# OpenDeck-r2_1_0.net
KiCad netlist of a schematic drawn in EAGLE
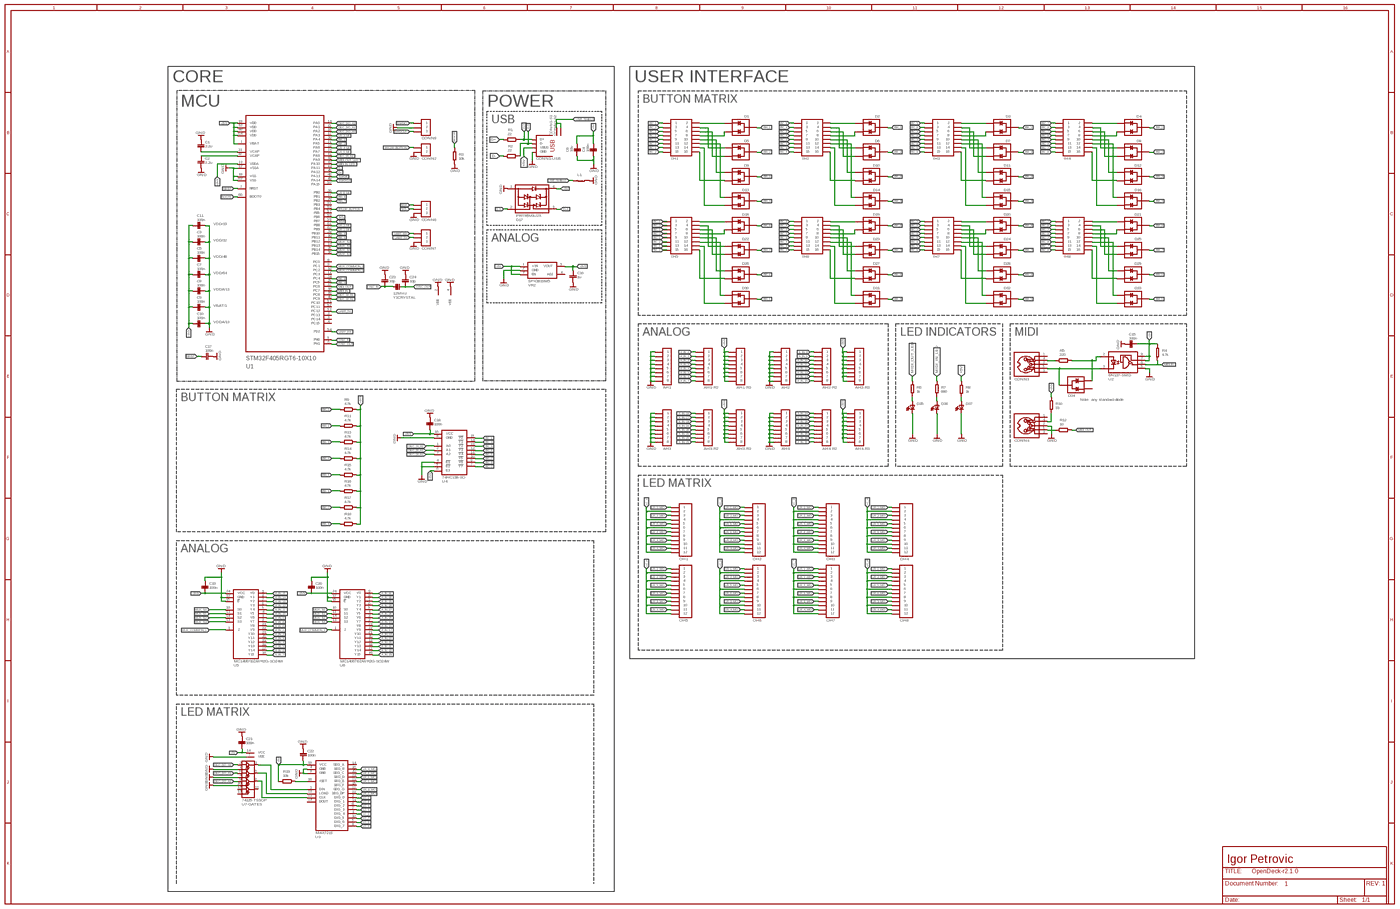
[diagram p0: schematic, sheet 1, overview]
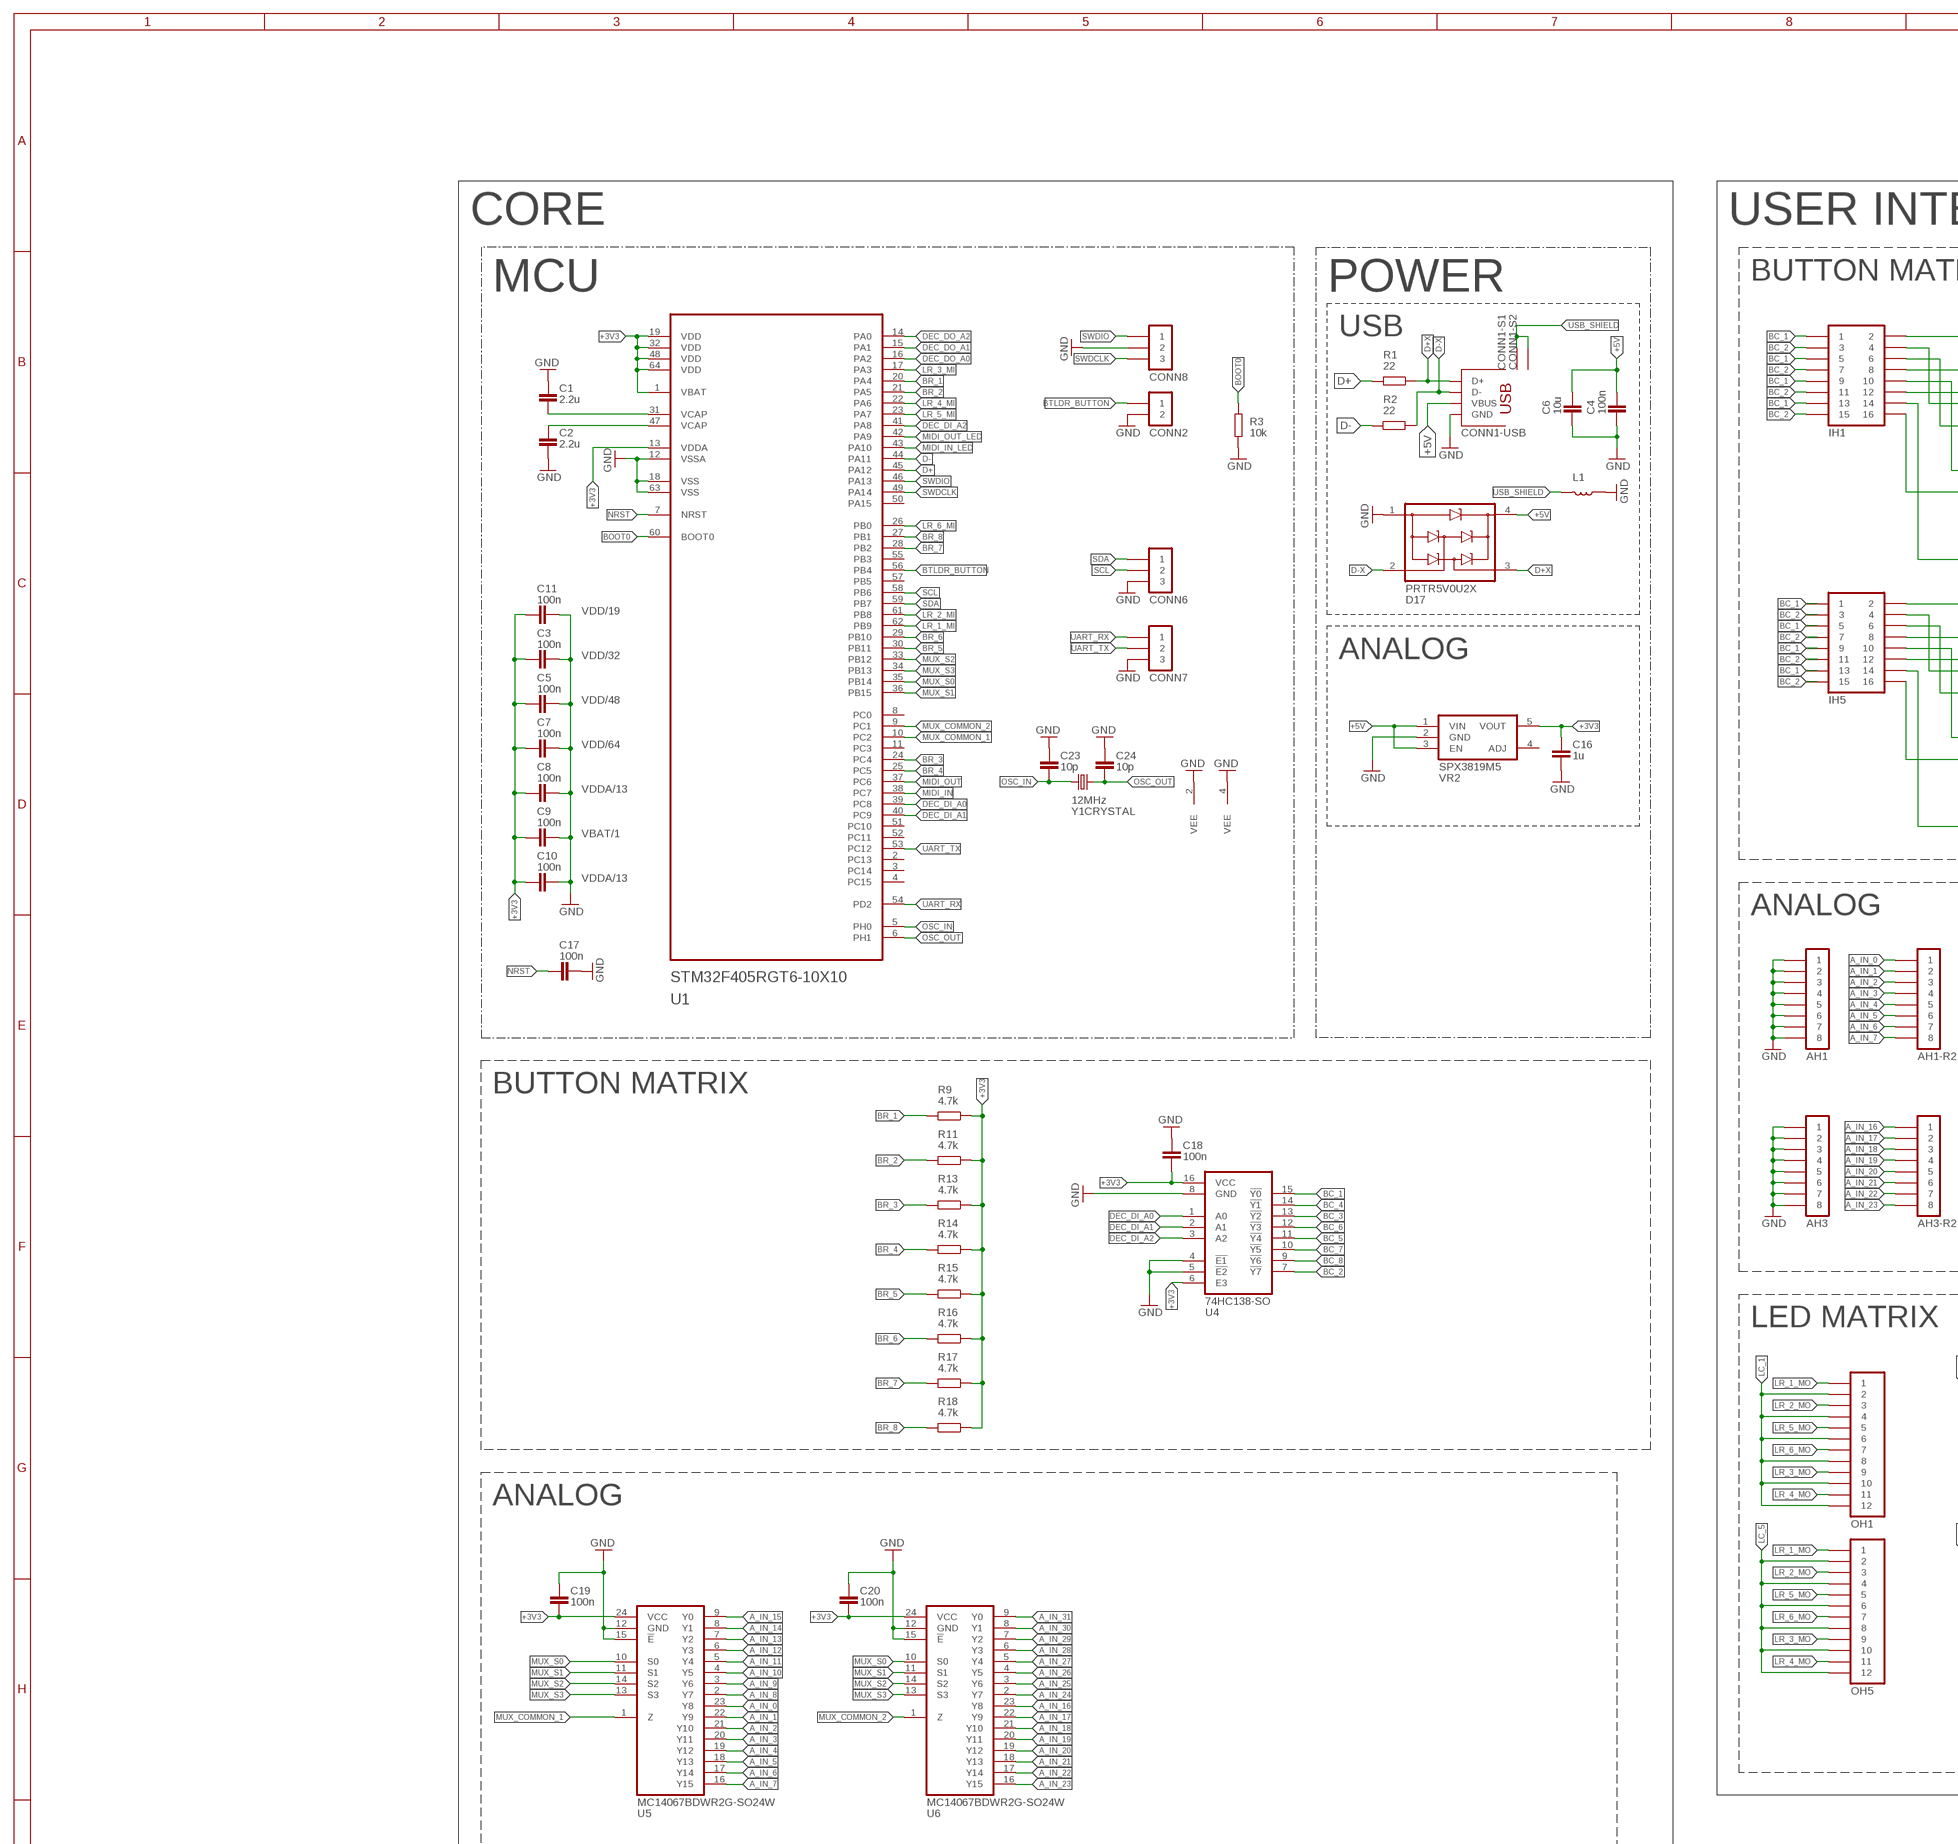
[diagram p1: schematic, sheet 1, part 1 of 4]
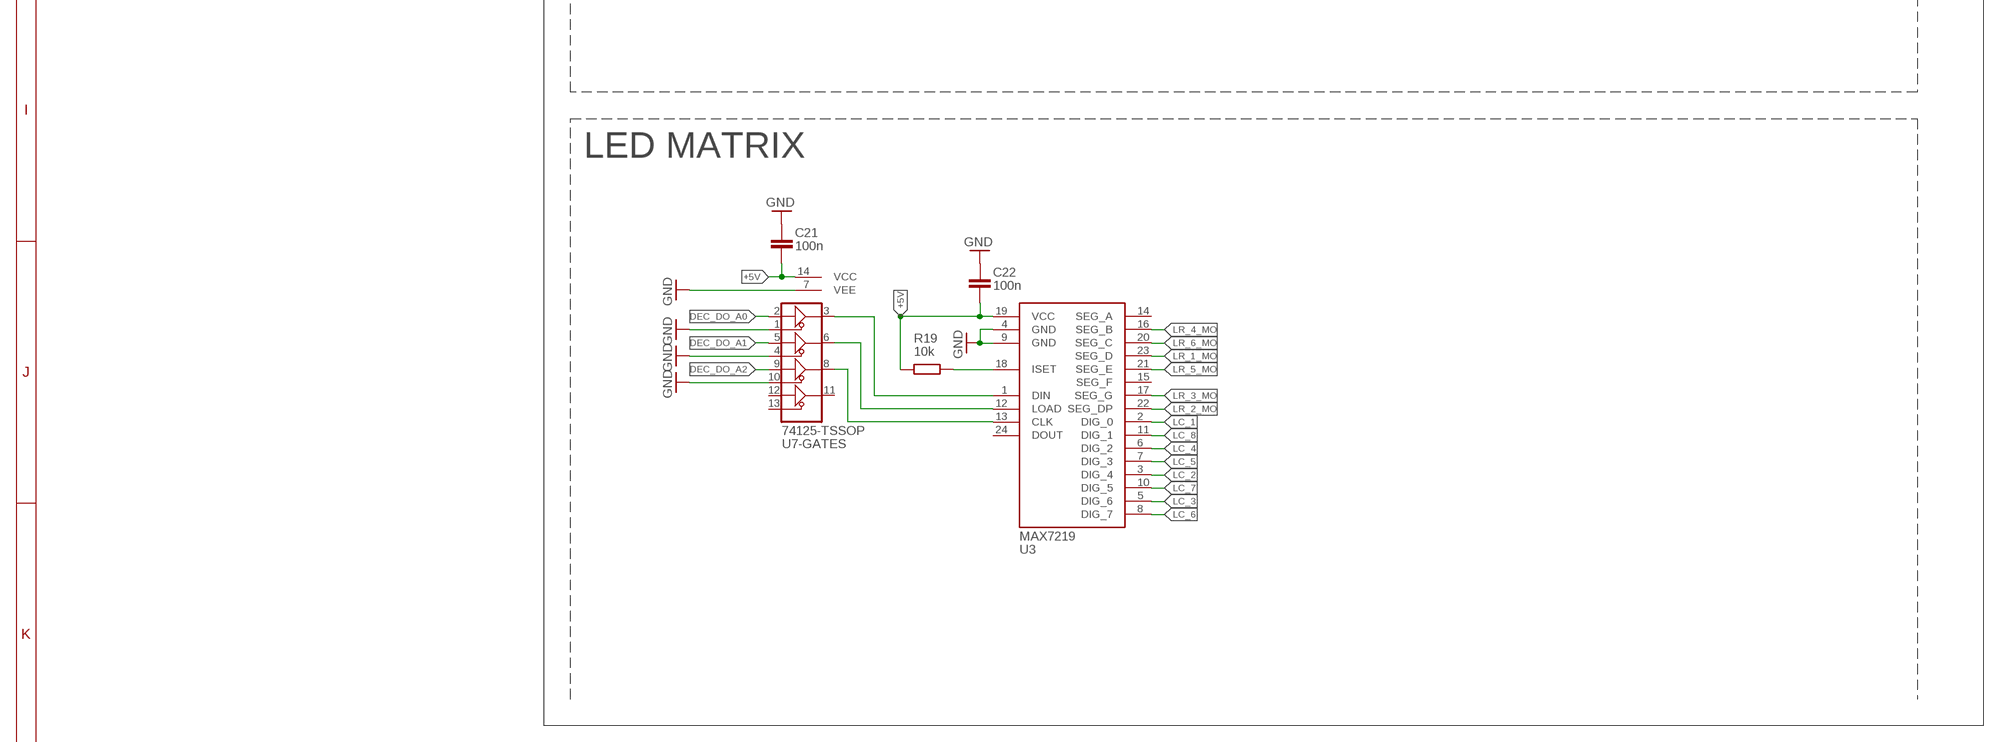
[diagram p2: schematic, sheet 1, part 2 of 4]
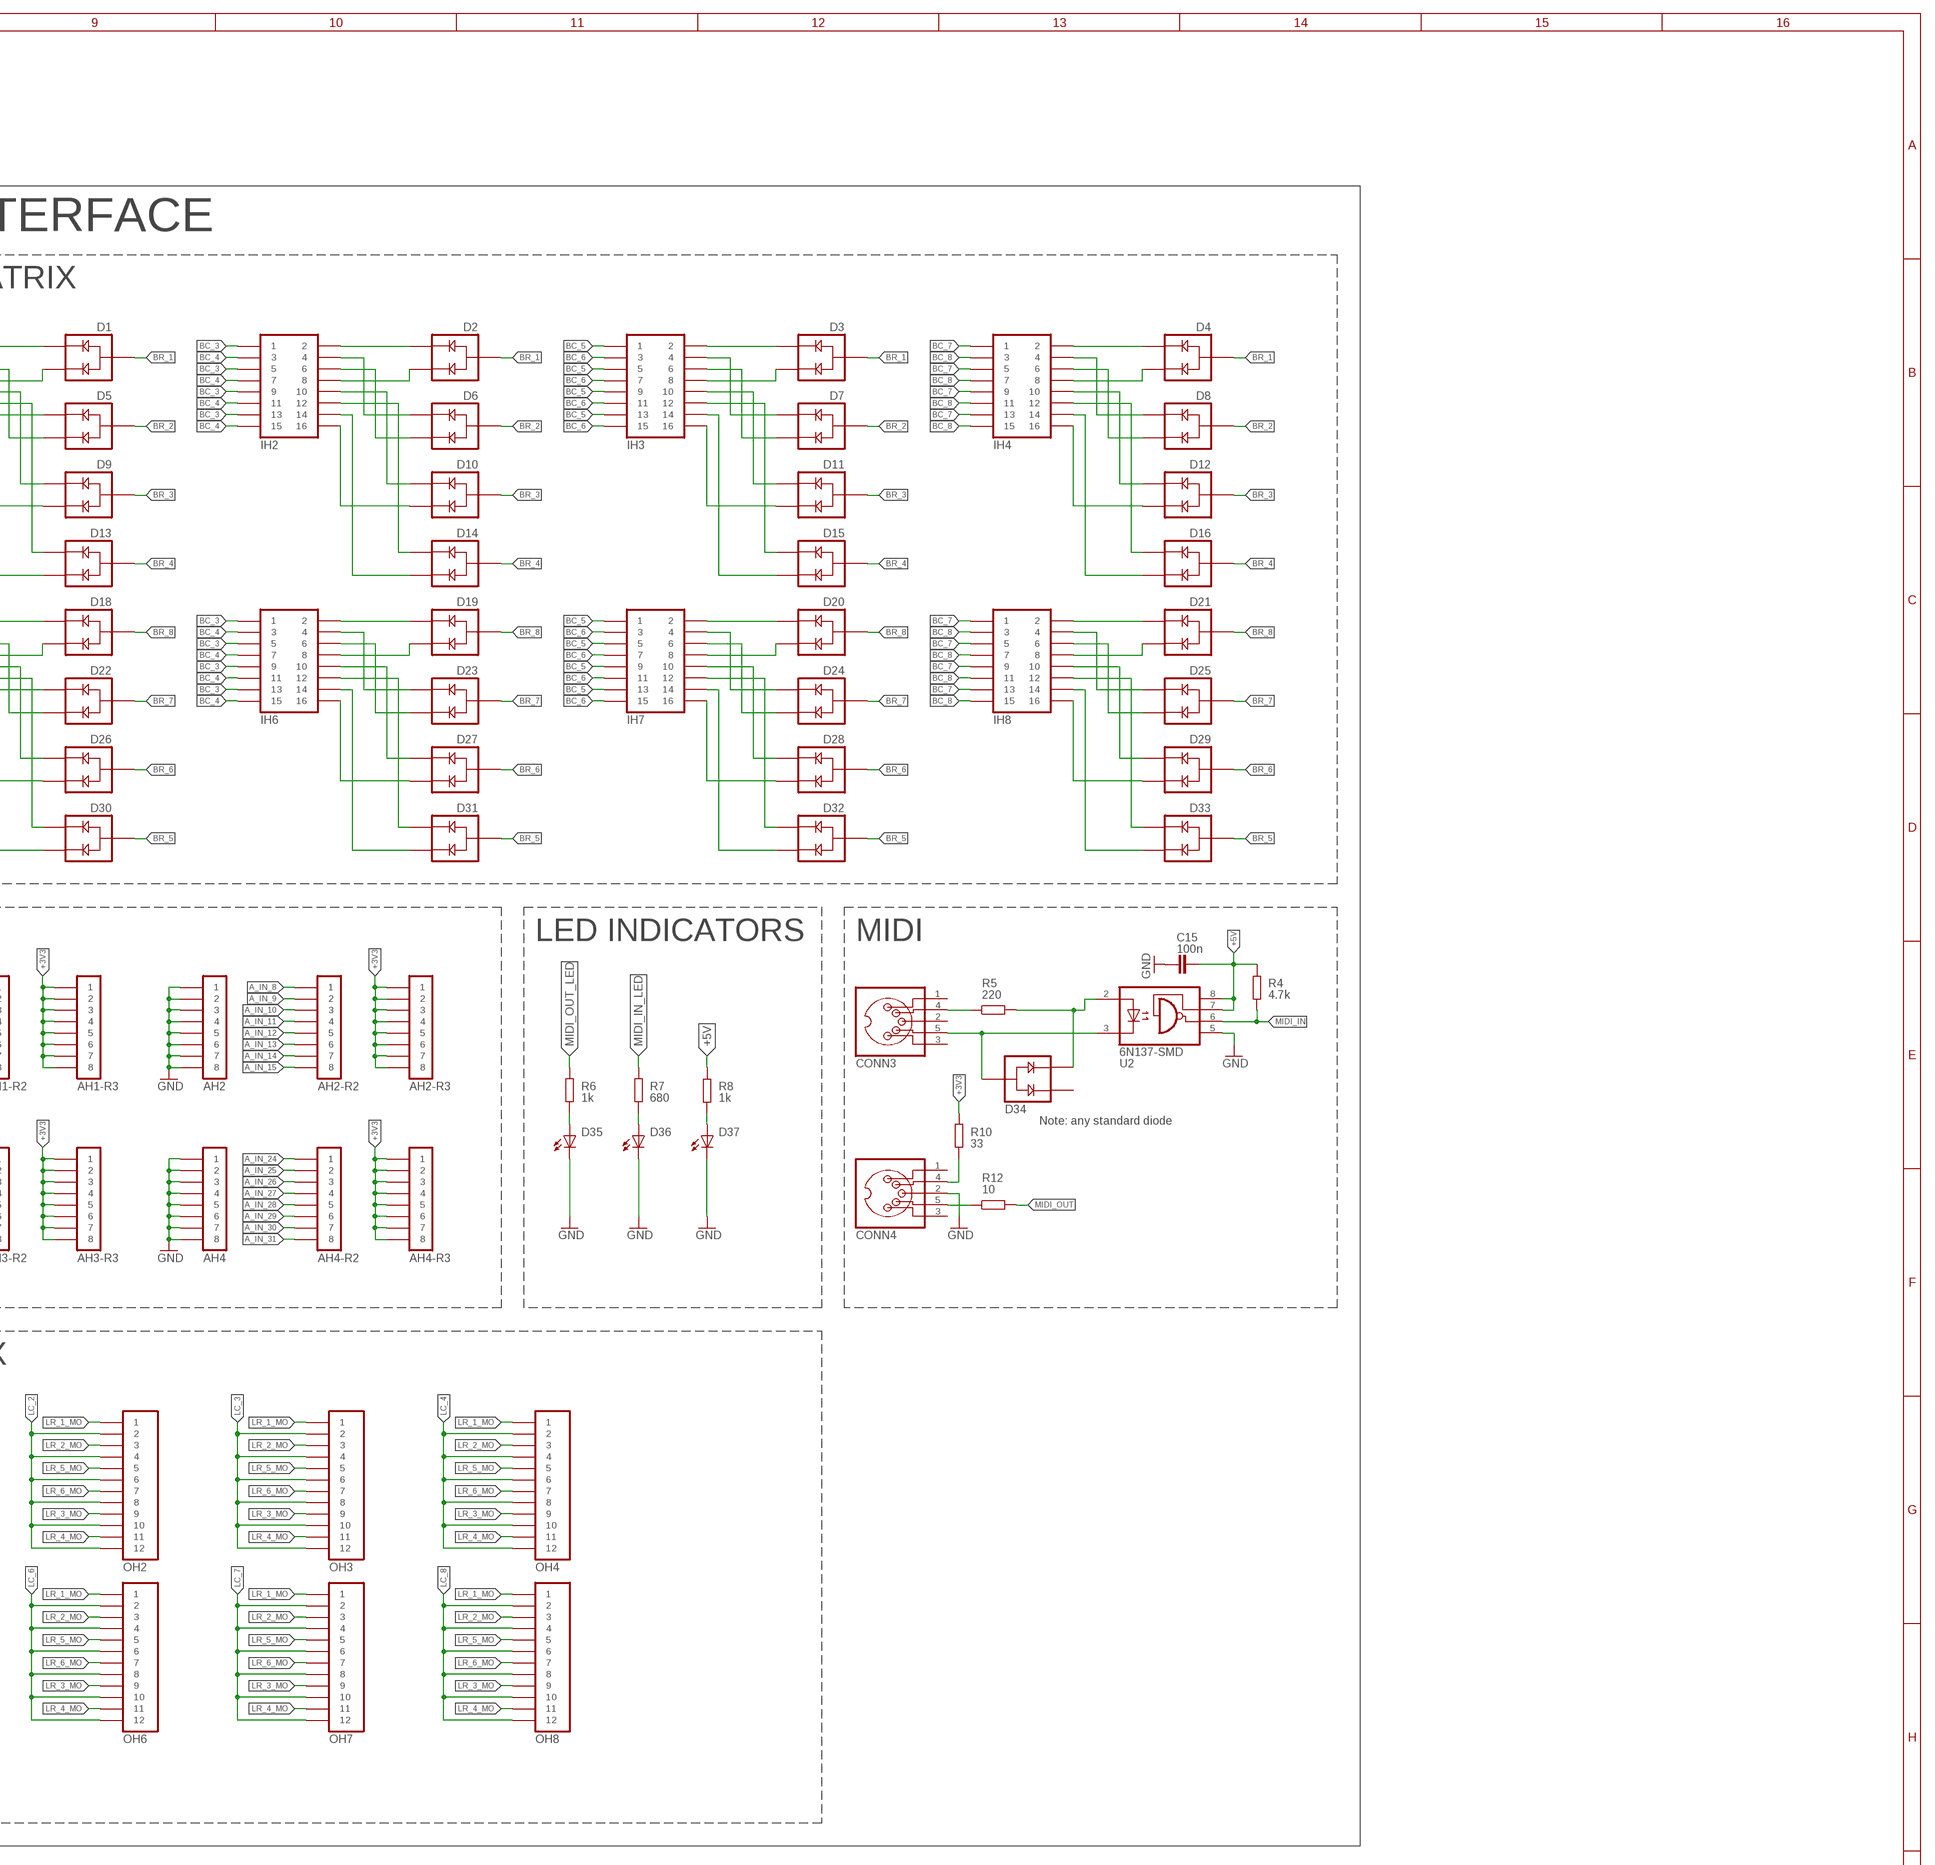
[diagram p3: schematic, sheet 1, part 3 of 4]
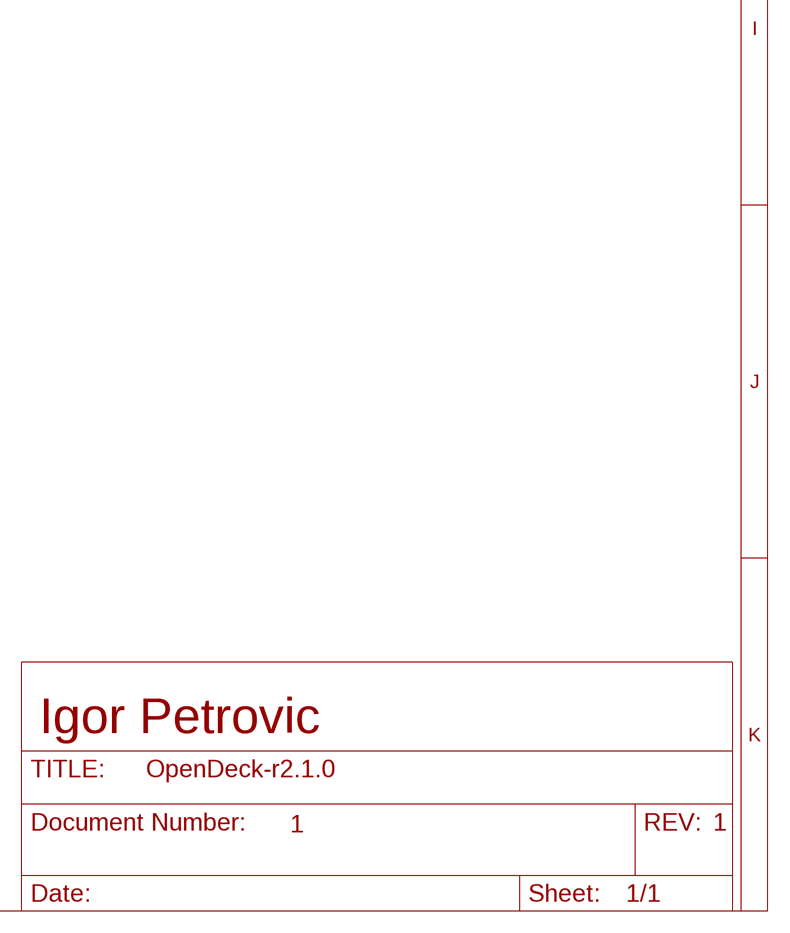
[diagram p4: schematic, sheet 1, part 4 of 4]

(export (version "E")
  (design (tool "Eeschema 10.0.6"))
  (components
    (comp (ref "AH1")
      (value "PINHD-3X08")
      (footprint "eagle-import:3X08-2.54")
      (libsource (lib "eagle-import") (part "PINHD-3X08"))
    )
    (comp (ref "AH2")
      (value "PINHD-3X08")
      (footprint "eagle-import:3X08-2.54")
      (libsource (lib "eagle-import") (part "PINHD-3X08"))
    )
    (comp (ref "AH3")
      (value "PINHD-3X08")
      (footprint "eagle-import:3X08-2.54")
      (libsource (lib "eagle-import") (part "PINHD-3X08"))
    )
    (comp (ref "AH4")
      (value "PINHD-3X08")
      (footprint "eagle-import:3X08-2.54")
      (libsource (lib "eagle-import") (part "PINHD-3X08"))
    )
    (comp (ref "C1")
      (value "2.2u")
      (footprint "eagle-import:C0402")
      (libsource (lib "eagle-import") (part "CAPACITOR-0402"))
    )
    (comp (ref "C2")
      (value "2.2u")
      (footprint "eagle-import:C0402")
      (libsource (lib "eagle-import") (part "CAPACITOR-0402"))
    )
    (comp (ref "C3")
      (value "100n")
      (footprint "eagle-import:C0402")
      (libsource (lib "eagle-import") (part "CAPACITOR-0402"))
    )
    (comp (ref "C4")
      (value "100n")
      (footprint "eagle-import:C0402")
      (libsource (lib "eagle-import") (part "CAPACITOR-0402"))
    )
    (comp (ref "C5")
      (value "100n")
      (footprint "eagle-import:C0402")
      (libsource (lib "eagle-import") (part "CAPACITOR-0402"))
    )
    (comp (ref "C6")
      (value "10u")
      (footprint "eagle-import:C0402")
      (libsource (lib "eagle-import") (part "CAPACITOR-0402"))
    )
    (comp (ref "C7")
      (value "100n")
      (footprint "eagle-import:C0402")
      (libsource (lib "eagle-import") (part "CAPACITOR-0402"))
    )
    (comp (ref "C8")
      (value "100n")
      (footprint "eagle-import:C0402")
      (libsource (lib "eagle-import") (part "CAPACITOR-0402"))
    )
    (comp (ref "C9")
      (value "100n")
      (footprint "eagle-import:C0402")
      (libsource (lib "eagle-import") (part "CAPACITOR-0402"))
    )
    (comp (ref "C10")
      (value "100n")
      (footprint "eagle-import:C0402")
      (libsource (lib "eagle-import") (part "CAPACITOR-0402"))
    )
    (comp (ref "C11")
      (value "100n")
      (footprint "eagle-import:C0402")
      (libsource (lib "eagle-import") (part "CAPACITOR-0402"))
    )
    (comp (ref "C15")
      (value "100n")
      (footprint "eagle-import:C0402")
      (libsource (lib "eagle-import") (part "CAPACITOR-0402"))
    )
    (comp (ref "C16")
      (value "1u")
      (footprint "eagle-import:C0402")
      (libsource (lib "eagle-import") (part "CAPACITOR-0402"))
    )
    (comp (ref "C17")
      (value "100n")
      (footprint "eagle-import:C0402")
      (libsource (lib "eagle-import") (part "CAPACITOR-0402"))
    )
    (comp (ref "C18")
      (value "100n")
      (footprint "eagle-import:C0402")
      (libsource (lib "eagle-import") (part "CAPACITOR-0402"))
    )
    (comp (ref "C19")
      (value "100n")
      (footprint "eagle-import:C0402")
      (libsource (lib "eagle-import") (part "CAPACITOR-0402"))
    )
    (comp (ref "C20")
      (value "100n")
      (footprint "eagle-import:C0402")
      (libsource (lib "eagle-import") (part "CAPACITOR-0402"))
    )
    (comp (ref "C21")
      (value "100n")
      (footprint "eagle-import:C0402")
      (libsource (lib "eagle-import") (part "CAPACITOR-0402"))
    )
    (comp (ref "C22")
      (value "100n")
      (footprint "eagle-import:C0402")
      (libsource (lib "eagle-import") (part "CAPACITOR-0402"))
    )
    (comp (ref "C23")
      (value "10p")
      (footprint "eagle-import:C0402")
      (libsource (lib "eagle-import") (part "CAPACITOR-0402"))
    )
    (comp (ref "C24")
      (value "10p")
      (footprint "eagle-import:C0402")
      (libsource (lib "eagle-import") (part "CAPACITOR-0402"))
    )
    (comp (ref "CONN1")
      (value "USB-B-H")
      (footprint "eagle-import:USB-B-PTH")
      (fields (field (name "LCSC") "C114097"))
      (libsource (lib "eagle-import") (part "USB-B-H"))
    )
    (comp (ref "CONN2")
      (value "PINHD-1X02-TH-2.54MM")
      (footprint "eagle-import:1X02-2.54-V")
      (libsource (lib "eagle-import") (part "PINHD-1X02-TH-2.54MM"))
    )
    (comp (ref "CONN3")
      (value "MIDI_CONN-STD")
      (footprint "eagle-import:DIN5")
      (fields (field (name "MANUFACTURER") "Switchcraft") (field (name "MPN") "57PC5F"))
      (libsource (lib "eagle-import") (part "MIDI_CONN-STD"))
    )
    (comp (ref "CONN4")
      (value "MIDI_CONN-STD")
      (footprint "eagle-import:DIN5")
      (fields (field (name "MANUFACTURER") "Switchcraft") (field (name "MPN") "57PC5F"))
      (libsource (lib "eagle-import") (part "MIDI_CONN-STD"))
    )
    (comp (ref "CONN6")
      (value "PINHD-1X03-TH-2.54MM")
      (footprint "eagle-import:1X03-2.54-V")
      (libsource (lib "eagle-import") (part "PINHD-1X03-TH-2.54MM"))
    )
    (comp (ref "CONN7")
      (value "PINHD-1X03-TH-2.54MM")
      (footprint "eagle-import:1X03-2.54-V")
      (libsource (lib "eagle-import") (part "PINHD-1X03-TH-2.54MM"))
    )
    (comp (ref "CONN8")
      (value "PINHD-1X03-TH-2.54MM")
      (footprint "eagle-import:1X03-2.54-V")
      (libsource (lib "eagle-import") (part "PINHD-1X03-TH-2.54MM"))
    )
    (comp (ref "D1")
      (value "BAW56")
      (footprint "eagle-import:SOT23")
      (fields (field (name "MANUFACTURER") "Multicomp") (field (name "MPN") "BAW56-7-F"))
      (libsource (lib "eagle-import") (part "BAW56"))
    )
    (comp (ref "D2")
      (value "BAW56")
      (footprint "eagle-import:SOT23")
      (fields (field (name "MANUFACTURER") "Multicomp") (field (name "MPN") "BAW56-7-F"))
      (libsource (lib "eagle-import") (part "BAW56"))
    )
    (comp (ref "D3")
      (value "BAW56")
      (footprint "eagle-import:SOT23")
      (fields (field (name "MANUFACTURER") "Multicomp") (field (name "MPN") "BAW56-7-F"))
      (libsource (lib "eagle-import") (part "BAW56"))
    )
    (comp (ref "D4")
      (value "BAW56")
      (footprint "eagle-import:SOT23")
      (fields (field (name "MANUFACTURER") "Multicomp") (field (name "MPN") "BAW56-7-F"))
      (libsource (lib "eagle-import") (part "BAW56"))
    )
    (comp (ref "D5")
      (value "BAW56")
      (footprint "eagle-import:SOT23")
      (fields (field (name "MANUFACTURER") "Multicomp") (field (name "MPN") "BAW56-7-F"))
      (libsource (lib "eagle-import") (part "BAW56"))
    )
    (comp (ref "D6")
      (value "BAW56")
      (footprint "eagle-import:SOT23")
      (fields (field (name "MANUFACTURER") "Multicomp") (field (name "MPN") "BAW56-7-F"))
      (libsource (lib "eagle-import") (part "BAW56"))
    )
    (comp (ref "D7")
      (value "BAW56")
      (footprint "eagle-import:SOT23")
      (fields (field (name "MANUFACTURER") "Multicomp") (field (name "MPN") "BAW56-7-F"))
      (libsource (lib "eagle-import") (part "BAW56"))
    )
    (comp (ref "D8")
      (value "BAW56")
      (footprint "eagle-import:SOT23")
      (fields (field (name "MANUFACTURER") "Multicomp") (field (name "MPN") "BAW56-7-F"))
      (libsource (lib "eagle-import") (part "BAW56"))
    )
    (comp (ref "D9")
      (value "BAW56")
      (footprint "eagle-import:SOT23")
      (fields (field (name "MANUFACTURER") "Multicomp") (field (name "MPN") "BAW56-7-F"))
      (libsource (lib "eagle-import") (part "BAW56"))
    )
    (comp (ref "D10")
      (value "BAW56")
      (footprint "eagle-import:SOT23")
      (fields (field (name "MANUFACTURER") "Multicomp") (field (name "MPN") "BAW56-7-F"))
      (libsource (lib "eagle-import") (part "BAW56"))
    )
    (comp (ref "D11")
      (value "BAW56")
      (footprint "eagle-import:SOT23")
      (fields (field (name "MANUFACTURER") "Multicomp") (field (name "MPN") "BAW56-7-F"))
      (libsource (lib "eagle-import") (part "BAW56"))
    )
    (comp (ref "D12")
      (value "BAW56")
      (footprint "eagle-import:SOT23")
      (fields (field (name "MANUFACTURER") "Multicomp") (field (name "MPN") "BAW56-7-F"))
      (libsource (lib "eagle-import") (part "BAW56"))
    )
    (comp (ref "D13")
      (value "BAW56")
      (footprint "eagle-import:SOT23")
      (fields (field (name "MANUFACTURER") "Multicomp") (field (name "MPN") "BAW56-7-F"))
      (libsource (lib "eagle-import") (part "BAW56"))
    )
    (comp (ref "D14")
      (value "BAW56")
      (footprint "eagle-import:SOT23")
      (fields (field (name "MANUFACTURER") "Multicomp") (field (name "MPN") "BAW56-7-F"))
      (libsource (lib "eagle-import") (part "BAW56"))
    )
    (comp (ref "D15")
      (value "BAW56")
      (footprint "eagle-import:SOT23")
      (fields (field (name "MANUFACTURER") "Multicomp") (field (name "MPN") "BAW56-7-F"))
      (libsource (lib "eagle-import") (part "BAW56"))
    )
    (comp (ref "D16")
      (value "BAW56")
      (footprint "eagle-import:SOT23")
      (fields (field (name "MANUFACTURER") "Multicomp") (field (name "MPN") "BAW56-7-F"))
      (libsource (lib "eagle-import") (part "BAW56"))
    )
    (comp (ref "D17")
      (value "PRTR5V0U2X")
      (footprint "eagle-import:SOT143")
      (fields (field (name "MANUFACTURER") "Nexperia"))
      (libsource (lib "eagle-import") (part "PRTR5V0U2X"))
    )
    (comp (ref "D18")
      (value "BAW56")
      (footprint "eagle-import:SOT23")
      (fields (field (name "MANUFACTURER") "Multicomp") (field (name "MPN") "BAW56-7-F"))
      (libsource (lib "eagle-import") (part "BAW56"))
    )
    (comp (ref "D19")
      (value "BAW56")
      (footprint "eagle-import:SOT23")
      (fields (field (name "MANUFACTURER") "Multicomp") (field (name "MPN") "BAW56-7-F"))
      (libsource (lib "eagle-import") (part "BAW56"))
    )
    (comp (ref "D20")
      (value "BAW56")
      (footprint "eagle-import:SOT23")
      (fields (field (name "MANUFACTURER") "Multicomp") (field (name "MPN") "BAW56-7-F"))
      (libsource (lib "eagle-import") (part "BAW56"))
    )
    (comp (ref "D21")
      (value "BAW56")
      (footprint "eagle-import:SOT23")
      (fields (field (name "MANUFACTURER") "Multicomp") (field (name "MPN") "BAW56-7-F"))
      (libsource (lib "eagle-import") (part "BAW56"))
    )
    (comp (ref "D22")
      (value "BAW56")
      (footprint "eagle-import:SOT23")
      (fields (field (name "MANUFACTURER") "Multicomp") (field (name "MPN") "BAW56-7-F"))
      (libsource (lib "eagle-import") (part "BAW56"))
    )
    (comp (ref "D23")
      (value "BAW56")
      (footprint "eagle-import:SOT23")
      (fields (field (name "MANUFACTURER") "Multicomp") (field (name "MPN") "BAW56-7-F"))
      (libsource (lib "eagle-import") (part "BAW56"))
    )
    (comp (ref "D24")
      (value "BAW56")
      (footprint "eagle-import:SOT23")
      (fields (field (name "MANUFACTURER") "Multicomp") (field (name "MPN") "BAW56-7-F"))
      (libsource (lib "eagle-import") (part "BAW56"))
    )
    (comp (ref "D25")
      (value "BAW56")
      (footprint "eagle-import:SOT23")
      (fields (field (name "MANUFACTURER") "Multicomp") (field (name "MPN") "BAW56-7-F"))
      (libsource (lib "eagle-import") (part "BAW56"))
    )
    (comp (ref "D26")
      (value "BAW56")
      (footprint "eagle-import:SOT23")
      (fields (field (name "MANUFACTURER") "Multicomp") (field (name "MPN") "BAW56-7-F"))
      (libsource (lib "eagle-import") (part "BAW56"))
    )
    (comp (ref "D27")
      (value "BAW56")
      (footprint "eagle-import:SOT23")
      (fields (field (name "MANUFACTURER") "Multicomp") (field (name "MPN") "BAW56-7-F"))
      (libsource (lib "eagle-import") (part "BAW56"))
    )
    (comp (ref "D28")
      (value "BAW56")
      (footprint "eagle-import:SOT23")
      (fields (field (name "MANUFACTURER") "Multicomp") (field (name "MPN") "BAW56-7-F"))
      (libsource (lib "eagle-import") (part "BAW56"))
    )
    (comp (ref "D29")
      (value "BAW56")
      (footprint "eagle-import:SOT23")
      (fields (field (name "MANUFACTURER") "Multicomp") (field (name "MPN") "BAW56-7-F"))
      (libsource (lib "eagle-import") (part "BAW56"))
    )
    (comp (ref "D30")
      (value "BAW56")
      (footprint "eagle-import:SOT23")
      (fields (field (name "MANUFACTURER") "Multicomp") (field (name "MPN") "BAW56-7-F"))
      (libsource (lib "eagle-import") (part "BAW56"))
    )
    (comp (ref "D31")
      (value "BAW56")
      (footprint "eagle-import:SOT23")
      (fields (field (name "MANUFACTURER") "Multicomp") (field (name "MPN") "BAW56-7-F"))
      (libsource (lib "eagle-import") (part "BAW56"))
    )
    (comp (ref "D32")
      (value "BAW56")
      (footprint "eagle-import:SOT23")
      (fields (field (name "MANUFACTURER") "Multicomp") (field (name "MPN") "BAW56-7-F"))
      (libsource (lib "eagle-import") (part "BAW56"))
    )
    (comp (ref "D33")
      (value "BAW56")
      (footprint "eagle-import:SOT23")
      (fields (field (name "MANUFACTURER") "Multicomp") (field (name "MPN") "BAW56-7-F"))
      (libsource (lib "eagle-import") (part "BAW56"))
    )
    (comp (ref "D34")
      (value "BAW56")
      (footprint "eagle-import:SOT23")
      (fields (field (name "MANUFACTURER") "Multicomp") (field (name "MPN") "BAW56-7-F"))
      (libsource (lib "eagle-import") (part "BAW56"))
    )
    (comp (ref "D35")
      (value "Red")
      (footprint "eagle-import:0805_LED")
      (libsource (lib "eagle-import") (part "LED-0805"))
    )
    (comp (ref "D36")
      (value "Yellow")
      (footprint "eagle-import:0805_LED")
      (libsource (lib "eagle-import") (part "LED-0805"))
    )
    (comp (ref "D37")
      (value "Green")
      (footprint "eagle-import:0805_LED")
      (libsource (lib "eagle-import") (part "LED-0805"))
    )
    (comp (ref "IH1")
      (value "PINHD-2X08-TH-2.54MM")
      (footprint "eagle-import:2X08-2.54")
      (libsource (lib "eagle-import") (part "PINHD-2X08-TH-2.54MM"))
    )
    (comp (ref "IH2")
      (value "PINHD-2X08-TH-2.54MM")
      (footprint "eagle-import:2X08-2.54")
      (libsource (lib "eagle-import") (part "PINHD-2X08-TH-2.54MM"))
    )
    (comp (ref "IH3")
      (value "PINHD-2X08-TH-2.54MM")
      (footprint "eagle-import:2X08-2.54")
      (libsource (lib "eagle-import") (part "PINHD-2X08-TH-2.54MM"))
    )
    (comp (ref "IH4")
      (value "PINHD-2X08-TH-2.54MM")
      (footprint "eagle-import:2X08-2.54")
      (libsource (lib "eagle-import") (part "PINHD-2X08-TH-2.54MM"))
    )
    (comp (ref "IH5")
      (value "PINHD-2X08-TH-2.54MM")
      (footprint "eagle-import:2X08-2.54")
      (libsource (lib "eagle-import") (part "PINHD-2X08-TH-2.54MM"))
    )
    (comp (ref "IH6")
      (value "PINHD-2X08-TH-2.54MM")
      (footprint "eagle-import:2X08-2.54")
      (libsource (lib "eagle-import") (part "PINHD-2X08-TH-2.54MM"))
    )
    (comp (ref "IH7")
      (value "PINHD-2X08-TH-2.54MM")
      (footprint "eagle-import:2X08-2.54")
      (libsource (lib "eagle-import") (part "PINHD-2X08-TH-2.54MM"))
    )
    (comp (ref "IH8")
      (value "PINHD-2X08-TH-2.54MM")
      (footprint "eagle-import:2X08-2.54")
      (libsource (lib "eagle-import") (part "PINHD-2X08-TH-2.54MM"))
    )
    (comp (ref "L1")
      (value "FERRITE_BEAD-BLM21PG221SN1D")
      (footprint "eagle-import:L0805")
      (fields (field (name "MANUFACTURER") "Murata") (field (name "MPN") "BLM21PG221SN1D"))
      (libsource (lib "eagle-import") (part "FERRITE_BEAD-BLM21PG221SN1D"))
    )
    (comp (ref "OH1")
      (value "PINHD-2X06-TH-2.54MM")
      (footprint "eagle-import:2X06-2.54-V")
      (libsource (lib "eagle-import") (part "PINHD-2X06-TH-2.54MM"))
    )
    (comp (ref "OH2")
      (value "PINHD-2X06-TH-2.54MM")
      (footprint "eagle-import:2X06-2.54-V")
      (libsource (lib "eagle-import") (part "PINHD-2X06-TH-2.54MM"))
    )
    (comp (ref "OH3")
      (value "PINHD-2X06-TH-2.54MM")
      (footprint "eagle-import:2X06-2.54-V")
      (libsource (lib "eagle-import") (part "PINHD-2X06-TH-2.54MM"))
    )
    (comp (ref "OH4")
      (value "PINHD-2X06-TH-2.54MM")
      (footprint "eagle-import:2X06-2.54-V")
      (libsource (lib "eagle-import") (part "PINHD-2X06-TH-2.54MM"))
    )
    (comp (ref "OH5")
      (value "PINHD-2X06-TH-2.54MM")
      (footprint "eagle-import:2X06-2.54-V")
      (libsource (lib "eagle-import") (part "PINHD-2X06-TH-2.54MM"))
    )
    (comp (ref "OH6")
      (value "PINHD-2X06-TH-2.54MM")
      (footprint "eagle-import:2X06-2.54-V")
      (libsource (lib "eagle-import") (part "PINHD-2X06-TH-2.54MM"))
    )
    (comp (ref "OH7")
      (value "PINHD-2X06-TH-2.54MM")
      (footprint "eagle-import:2X06-2.54-V")
      (libsource (lib "eagle-import") (part "PINHD-2X06-TH-2.54MM"))
    )
    (comp (ref "OH8")
      (value "PINHD-2X06-TH-2.54MM")
      (footprint "eagle-import:2X06-2.54-V")
      (libsource (lib "eagle-import") (part "PINHD-2X06-TH-2.54MM"))
    )
    (comp (ref "R1")
      (value "22")
      (footprint "eagle-import:R0402")
      (libsource (lib "eagle-import") (part "RESISTOR-0402"))
    )
    (comp (ref "R2")
      (value "22")
      (footprint "eagle-import:R0402")
      (libsource (lib "eagle-import") (part "RESISTOR-0402"))
    )
    (comp (ref "R3")
      (value "10k")
      (footprint "eagle-import:R0402")
      (libsource (lib "eagle-import") (part "RESISTOR-0402"))
    )
    (comp (ref "R4")
      (value "4.7k")
      (footprint "eagle-import:R0402")
      (libsource (lib "eagle-import") (part "RESISTOR-0402"))
    )
    (comp (ref "R5")
      (value "220")
      (footprint "eagle-import:R0402")
      (libsource (lib "eagle-import") (part "RESISTOR-0402"))
    )
    (comp (ref "R6")
      (value "1k")
      (footprint "eagle-import:R0402")
      (libsource (lib "eagle-import") (part "RESISTOR-0402"))
    )
    (comp (ref "R7")
      (value "680")
      (footprint "eagle-import:R0402")
      (libsource (lib "eagle-import") (part "RESISTOR-0402"))
    )
    (comp (ref "R8")
      (value "1k")
      (footprint "eagle-import:R0402")
      (libsource (lib "eagle-import") (part "RESISTOR-0402"))
    )
    (comp (ref "R9")
      (value "4.7k")
      (footprint "eagle-import:R0402")
      (libsource (lib "eagle-import") (part "RESISTOR-0402"))
    )
    (comp (ref "R10")
      (value "33")
      (footprint "eagle-import:R0402")
      (libsource (lib "eagle-import") (part "RESISTOR-0402"))
    )
    (comp (ref "R11")
      (value "4.7k")
      (footprint "eagle-import:R0402")
      (libsource (lib "eagle-import") (part "RESISTOR-0402"))
    )
    (comp (ref "R12")
      (value "10")
      (footprint "eagle-import:R0402")
      (libsource (lib "eagle-import") (part "RESISTOR-0402"))
    )
    (comp (ref "R13")
      (value "4.7k")
      (footprint "eagle-import:R0402")
      (libsource (lib "eagle-import") (part "RESISTOR-0402"))
    )
    (comp (ref "R14")
      (value "4.7k")
      (footprint "eagle-import:R0402")
      (libsource (lib "eagle-import") (part "RESISTOR-0402"))
    )
    (comp (ref "R15")
      (value "4.7k")
      (footprint "eagle-import:R0402")
      (libsource (lib "eagle-import") (part "RESISTOR-0402"))
    )
    (comp (ref "R16")
      (value "4.7k")
      (footprint "eagle-import:R0402")
      (libsource (lib "eagle-import") (part "RESISTOR-0402"))
    )
    (comp (ref "R17")
      (value "4.7k")
      (footprint "eagle-import:R0402")
      (libsource (lib "eagle-import") (part "RESISTOR-0402"))
    )
    (comp (ref "R18")
      (value "4.7k")
      (footprint "eagle-import:R0402")
      (libsource (lib "eagle-import") (part "RESISTOR-0402"))
    )
    (comp (ref "R19")
      (value "10k")
      (footprint "eagle-import:R0402")
      (libsource (lib "eagle-import") (part "RESISTOR-0402"))
    )
    (comp (ref "U1")
      (value "STM32F405RGT6-10X10")
      (footprint "eagle-import:TQFP-64-10X10")
      (fields (field (name "MANUFACTURER") "ST Microelectronics") (field (name "MPN") "STM32F405RGT6"))
      (libsource (lib "eagle-import") (part "STM32F405RGT6-10X10"))
    )
    (comp (ref "U2")
      (value "6N137-SMD")
      (footprint "eagle-import:SMD-8")
      (fields (field (name "MANUFACTURER") "Lite-On") (field (name "MPN") "6N137S"))
      (libsource (lib "eagle-import") (part "6N137-SMD"))
    )
    (comp (ref "U3")
      (value "MAX7219")
      (footprint "eagle-import:SO24-W")
      (libsource (lib "eagle-import") (part "MAX7219"))
    )
    (comp (ref "U4")
      (value "74HC138-SO")
      (footprint "eagle-import:SO16")
      (fields (field (name "MANUFACTURER") "Nexperia") (field (name "MPN") "74HC138D"))
      (libsource (lib "eagle-import") (part "74138-SOHC"))
    )
    (comp (ref "U5")
      (value "MC14067BDWR2G-SO24W")
      (footprint "eagle-import:SO24-W")
      (fields (field (name "MANUFACTURER") "ON Semiconductor") (field (name "MPN") "MC14067BDWR2G"))
      (libsource (lib "eagle-import") (part "MC14067BDWR2G-SO24W"))
    )
    (comp (ref "U6")
      (value "MC14067BDWR2G-SO24W")
      (footprint "eagle-import:SO24-W")
      (fields (field (name "MANUFACTURER") "ON Semiconductor") (field (name "MPN") "MC14067BDWR2G"))
      (libsource (lib "eagle-import") (part "MC14067BDWR2G-SO24W"))
    )
    (comp (ref "U7")
      (value "74125-TSSOP")
      (footprint "eagle-import:TSSOP14")
      (fields (field (name "LCSC") "C36365"))
      (libsource (lib "eagle-import") (part "74125-TSSOP"))
    )
    (comp (ref "VR2")
      (value "SPX3819M5")
      (footprint "eagle-import:SOT23-5")
      (libsource (lib "eagle-import") (part "SPX3819M5"))
    )
    (comp (ref "Y1")
      (value "12MHz")
      (footprint "eagle-import:CRYSTAL-SMD-2.5X2")
      (fields
        (field (name "MANUFACTURER") "ECS")
        (field (name "MPN") "ECS-160-10-36-CKM-TR")
        (field (name "LCSC") "C254284")
      )
      (libsource (lib "eagle-import") (part "CRYSTAL-4P-SMD-2.5X2"))
    )
  )
  (nets
    (net (code "1") (name "+3V3") (class "Default")
      (node (ref "AH1") (pin "12") (pinfunction "4_12") (pintype "passive"))
      (node (ref "AH1") (pin "15") (pinfunction "5_15") (pintype "passive"))
      (node (ref "AH1") (pin "18") (pinfunction "6_18") (pintype "passive"))
      (node (ref "AH1") (pin "21") (pinfunction "7_21") (pintype "passive"))
      (node (ref "AH1") (pin "24") (pinfunction "8_24") (pintype "passive"))
      (node (ref "AH1") (pin "3") (pinfunction "1_3") (pintype "passive"))
      (node (ref "AH1") (pin "6") (pinfunction "2_6") (pintype "passive"))
      (node (ref "AH1") (pin "9") (pinfunction "3_9") (pintype "passive"))
      (node (ref "AH2") (pin "12") (pinfunction "4_12") (pintype "passive"))
      (node (ref "AH2") (pin "15") (pinfunction "5_15") (pintype "passive"))
      (node (ref "AH2") (pin "18") (pinfunction "6_18") (pintype "passive"))
      (node (ref "AH2") (pin "21") (pinfunction "7_21") (pintype "passive"))
      (node (ref "AH2") (pin "24") (pinfunction "8_24") (pintype "passive"))
      (node (ref "AH2") (pin "3") (pinfunction "1_3") (pintype "passive"))
      (node (ref "AH2") (pin "6") (pinfunction "2_6") (pintype "passive"))
      (node (ref "AH2") (pin "9") (pinfunction "3_9") (pintype "passive"))
      (node (ref "AH3") (pin "12") (pinfunction "4_12") (pintype "passive"))
      (node (ref "AH3") (pin "15") (pinfunction "5_15") (pintype "passive"))
      (node (ref "AH3") (pin "18") (pinfunction "6_18") (pintype "passive"))
      (node (ref "AH3") (pin "21") (pinfunction "7_21") (pintype "passive"))
      (node (ref "AH3") (pin "24") (pinfunction "8_24") (pintype "passive"))
      (node (ref "AH3") (pin "3") (pinfunction "1_3") (pintype "passive"))
      (node (ref "AH3") (pin "6") (pinfunction "2_6") (pintype "passive"))
      (node (ref "AH3") (pin "9") (pinfunction "3_9") (pintype "passive"))
      (node (ref "AH4") (pin "12") (pinfunction "4_12") (pintype "passive"))
      (node (ref "AH4") (pin "15") (pinfunction "5_15") (pintype "passive"))
      (node (ref "AH4") (pin "18") (pinfunction "6_18") (pintype "passive"))
      (node (ref "AH4") (pin "21") (pinfunction "7_21") (pintype "passive"))
      (node (ref "AH4") (pin "24") (pinfunction "8_24") (pintype "passive"))
      (node (ref "AH4") (pin "3") (pinfunction "1_3") (pintype "passive"))
      (node (ref "AH4") (pin "6") (pinfunction "2_6") (pintype "passive"))
      (node (ref "AH4") (pin "9") (pinfunction "3_9") (pintype "passive"))
      (node (ref "C10") (pin "1") (pinfunction "1_1") (pintype "passive"))
      (node (ref "C11") (pin "1") (pinfunction "1_1") (pintype "passive"))
      (node (ref "C16") (pin "1") (pinfunction "1_1") (pintype "passive"))
      (node (ref "C18") (pin "2") (pinfunction "2_2") (pintype "passive"))
      (node (ref "C19") (pin "2") (pinfunction "2_2") (pintype "passive"))
      (node (ref "C20") (pin "2") (pinfunction "2_2") (pintype "passive"))
      (node (ref "C3") (pin "1") (pinfunction "1_1") (pintype "passive"))
      (node (ref "C5") (pin "1") (pinfunction "1_1") (pintype "passive"))
      (node (ref "C7") (pin "1") (pinfunction "1_1") (pintype "passive"))
      (node (ref "C8") (pin "1") (pinfunction "1_1") (pintype "passive"))
      (node (ref "C9") (pin "1") (pinfunction "1_1") (pintype "passive"))
      (node (ref "R10") (pin "2") (pinfunction "2_2") (pintype "passive"))
      (node (ref "R11") (pin "1") (pinfunction "1_1") (pintype "passive"))
      (node (ref "R13") (pin "1") (pinfunction "1_1") (pintype "passive"))
      (node (ref "R14") (pin "1") (pinfunction "1_1") (pintype "passive"))
      (node (ref "R15") (pin "1") (pinfunction "1_1") (pintype "passive"))
      (node (ref "R16") (pin "1") (pinfunction "1_1") (pintype "passive"))
      (node (ref "R17") (pin "1") (pinfunction "1_1") (pintype "passive"))
      (node (ref "R18") (pin "1") (pinfunction "1_1") (pintype "passive"))
      (node (ref "R9") (pin "1") (pinfunction "1_1") (pintype "passive"))
      (node (ref "U1") (pin "1") (pinfunction "VBAT_1") (pintype "bidirectional"))
      (node (ref "U1") (pin "13") (pinfunction "VDDA_13") (pintype "bidirectional"))
      (node (ref "U1") (pin "19") (pinfunction "VDD_19") (pintype "bidirectional"))
      (node (ref "U1") (pin "32") (pinfunction "VDD_32") (pintype "bidirectional"))
      (node (ref "U1") (pin "48") (pinfunction "VDD_48") (pintype "bidirectional"))
      (node (ref "U1") (pin "64") (pinfunction "VDD_64") (pintype "bidirectional"))
      (node (ref "U4") (pin "16") (pinfunction "VCC_16") (pintype "power_in"))
      (node (ref "U4") (pin "6") (pinfunction "E3_6") (pintype "input"))
      (node (ref "U5") (pin "24") (pinfunction "VCC_24") (pintype "passive"))
      (node (ref "U6") (pin "24") (pinfunction "VCC_24") (pintype "passive"))
      (node (ref "VR2") (pin "5") (pinfunction "VOUT_5") (pintype "passive"))
    )
    (net (code "2") (name "+5V") (class "Default")
      (node (ref "C15") (pin "2") (pinfunction "2_2") (pintype "passive"))
      (node (ref "C21") (pin "1") (pinfunction "1_1") (pintype "passive"))
      (node (ref "C22") (pin "1") (pinfunction "1_1") (pintype "passive"))
      (node (ref "C4") (pin "2") (pinfunction "2_2") (pintype "passive"))
      (node (ref "C6") (pin "2") (pinfunction "2_2") (pintype "passive"))
      (node (ref "CONN1") (pin "VBUS") (pinfunction "VBUS_VBUS") (pintype "bidirectional"))
      (node (ref "D17") (pin "4") (pinfunction "VCC_4") (pintype "passive"))
      (node (ref "R19") (pin "2") (pinfunction "2_2") (pintype "passive"))
      (node (ref "R4") (pin "1") (pinfunction "1_1") (pintype "passive"))
      (node (ref "R8") (pin "1") (pinfunction "1_1") (pintype "passive"))
      (node (ref "U2") (pin "7") (pinfunction "VE_7") (pintype "input"))
      (node (ref "U2") (pin "8") (pinfunction "VCC_8") (pintype "power_in"))
      (node (ref "U3") (pin "19") (pinfunction "VCC_19") (pintype "power_in"))
      (node (ref "U7") (pin "14") (pinfunction "VCC_14") (pintype "passive"))
      (node (ref "VR2") (pin "1") (pinfunction "VIN_1") (pintype "passive"))
      (node (ref "VR2") (pin "3") (pinfunction "EN_3") (pintype "passive"))
    )
    (net (code "3") (name "A_IN_0") (class "Default")
      (node (ref "AH1") (pin "2") (pinfunction "1_2") (pintype "passive"))
      (node (ref "U5") (pin "23") (pinfunction "Y8_23") (pintype "bidirectional"))
    )
    (net (code "4") (name "A_IN_1") (class "Default")
      (node (ref "AH1") (pin "5") (pinfunction "2_5") (pintype "passive"))
      (node (ref "U5") (pin "22") (pinfunction "Y9_22") (pintype "bidirectional"))
    )
    (net (code "5") (name "A_IN_2") (class "Default")
      (node (ref "AH1") (pin "8") (pinfunction "3_8") (pintype "passive"))
      (node (ref "U5") (pin "21") (pinfunction "Y10_21") (pintype "bidirectional"))
    )
    (net (code "6") (name "A_IN_3") (class "Default")
      (node (ref "AH1") (pin "11") (pinfunction "4_11") (pintype "passive"))
      (node (ref "U5") (pin "20") (pinfunction "Y11_20") (pintype "bidirectional"))
    )
    (net (code "7") (name "A_IN_4") (class "Default")
      (node (ref "AH1") (pin "14") (pinfunction "5_14") (pintype "passive"))
      (node (ref "U5") (pin "19") (pinfunction "Y12_19") (pintype "bidirectional"))
    )
    (net (code "8") (name "A_IN_5") (class "Default")
      (node (ref "AH1") (pin "17") (pinfunction "6_17") (pintype "passive"))
      (node (ref "U5") (pin "18") (pinfunction "Y13_18") (pintype "bidirectional"))
    )
    (net (code "9") (name "A_IN_6") (class "Default")
      (node (ref "AH1") (pin "20") (pinfunction "7_20") (pintype "passive"))
      (node (ref "U5") (pin "17") (pinfunction "Y14_17") (pintype "bidirectional"))
    )
    (net (code "10") (name "A_IN_7") (class "Default")
      (node (ref "AH1") (pin "23") (pinfunction "8_23") (pintype "passive"))
      (node (ref "U5") (pin "16") (pinfunction "Y15_16") (pintype "bidirectional"))
    )
    (net (code "11") (name "A_IN_8") (class "Default")
      (node (ref "AH2") (pin "2") (pinfunction "1_2") (pintype "passive"))
      (node (ref "U5") (pin "2") (pinfunction "Y7_2") (pintype "bidirectional"))
    )
    (net (code "12") (name "A_IN_9") (class "Default")
      (node (ref "AH2") (pin "5") (pinfunction "2_5") (pintype "passive"))
      (node (ref "U5") (pin "3") (pinfunction "Y6_3") (pintype "bidirectional"))
    )
    (net (code "13") (name "A_IN_10") (class "Default")
      (node (ref "AH2") (pin "8") (pinfunction "3_8") (pintype "passive"))
      (node (ref "U5") (pin "4") (pinfunction "Y5_4") (pintype "bidirectional"))
    )
    (net (code "14") (name "A_IN_11") (class "Default")
      (node (ref "AH2") (pin "11") (pinfunction "4_11") (pintype "passive"))
      (node (ref "U5") (pin "5") (pinfunction "Y4_5") (pintype "bidirectional"))
    )
    (net (code "15") (name "A_IN_12") (class "Default")
      (node (ref "AH2") (pin "14") (pinfunction "5_14") (pintype "passive"))
      (node (ref "U5") (pin "6") (pinfunction "Y3_6") (pintype "bidirectional"))
    )
    (net (code "16") (name "A_IN_13") (class "Default")
      (node (ref "AH2") (pin "17") (pinfunction "6_17") (pintype "passive"))
      (node (ref "U5") (pin "7") (pinfunction "Y2_7") (pintype "bidirectional"))
    )
    (net (code "17") (name "A_IN_14") (class "Default")
      (node (ref "AH2") (pin "20") (pinfunction "7_20") (pintype "passive"))
      (node (ref "U5") (pin "8") (pinfunction "Y1_8") (pintype "bidirectional"))
    )
    (net (code "18") (name "A_IN_15") (class "Default")
      (node (ref "AH2") (pin "23") (pinfunction "8_23") (pintype "passive"))
      (node (ref "U5") (pin "9") (pinfunction "Y0_9") (pintype "bidirectional"))
    )
    (net (code "19") (name "A_IN_16") (class "Default")
      (node (ref "AH3") (pin "2") (pinfunction "1_2") (pintype "passive"))
      (node (ref "U6") (pin "23") (pinfunction "Y8_23") (pintype "bidirectional"))
    )
    (net (code "20") (name "A_IN_17") (class "Default")
      (node (ref "AH3") (pin "5") (pinfunction "2_5") (pintype "passive"))
      (node (ref "U6") (pin "22") (pinfunction "Y9_22") (pintype "bidirectional"))
    )
    (net (code "21") (name "A_IN_18") (class "Default")
      (node (ref "AH3") (pin "8") (pinfunction "3_8") (pintype "passive"))
      (node (ref "U6") (pin "21") (pinfunction "Y10_21") (pintype "bidirectional"))
    )
    (net (code "22") (name "A_IN_19") (class "Default")
      (node (ref "AH3") (pin "11") (pinfunction "4_11") (pintype "passive"))
      (node (ref "U6") (pin "20") (pinfunction "Y11_20") (pintype "bidirectional"))
    )
    (net (code "23") (name "A_IN_20") (class "Default")
      (node (ref "AH3") (pin "14") (pinfunction "5_14") (pintype "passive"))
      (node (ref "U6") (pin "19") (pinfunction "Y12_19") (pintype "bidirectional"))
    )
    (net (code "24") (name "A_IN_21") (class "Default")
      (node (ref "AH3") (pin "17") (pinfunction "6_17") (pintype "passive"))
      (node (ref "U6") (pin "18") (pinfunction "Y13_18") (pintype "bidirectional"))
    )
    (net (code "25") (name "A_IN_22") (class "Default")
      (node (ref "AH3") (pin "20") (pinfunction "7_20") (pintype "passive"))
      (node (ref "U6") (pin "17") (pinfunction "Y14_17") (pintype "bidirectional"))
    )
    (net (code "26") (name "A_IN_23") (class "Default")
      (node (ref "AH3") (pin "23") (pinfunction "8_23") (pintype "passive"))
      (node (ref "U6") (pin "16") (pinfunction "Y15_16") (pintype "bidirectional"))
    )
    (net (code "27") (name "A_IN_24") (class "Default")
      (node (ref "AH4") (pin "2") (pinfunction "1_2") (pintype "passive"))
      (node (ref "U6") (pin "2") (pinfunction "Y7_2") (pintype "bidirectional"))
    )
    (net (code "28") (name "A_IN_25") (class "Default")
      (node (ref "AH4") (pin "5") (pinfunction "2_5") (pintype "passive"))
      (node (ref "U6") (pin "3") (pinfunction "Y6_3") (pintype "bidirectional"))
    )
    (net (code "29") (name "A_IN_26") (class "Default")
      (node (ref "AH4") (pin "8") (pinfunction "3_8") (pintype "passive"))
      (node (ref "U6") (pin "4") (pinfunction "Y5_4") (pintype "bidirectional"))
    )
    (net (code "30") (name "A_IN_27") (class "Default")
      (node (ref "AH4") (pin "11") (pinfunction "4_11") (pintype "passive"))
      (node (ref "U6") (pin "5") (pinfunction "Y4_5") (pintype "bidirectional"))
    )
    (net (code "31") (name "A_IN_28") (class "Default")
      (node (ref "AH4") (pin "14") (pinfunction "5_14") (pintype "passive"))
      (node (ref "U6") (pin "6") (pinfunction "Y3_6") (pintype "bidirectional"))
    )
    (net (code "32") (name "A_IN_29") (class "Default")
      (node (ref "AH4") (pin "17") (pinfunction "6_17") (pintype "passive"))
      (node (ref "U6") (pin "7") (pinfunction "Y2_7") (pintype "bidirectional"))
    )
    (net (code "33") (name "A_IN_30") (class "Default")
      (node (ref "AH4") (pin "20") (pinfunction "7_20") (pintype "passive"))
      (node (ref "U6") (pin "8") (pinfunction "Y1_8") (pintype "bidirectional"))
    )
    (net (code "34") (name "A_IN_31") (class "Default")
      (node (ref "AH4") (pin "23") (pinfunction "8_23") (pintype "passive"))
      (node (ref "U6") (pin "9") (pinfunction "Y0_9") (pintype "bidirectional"))
    )
    (net (code "35") (name "BC_1") (class "Default")
      (node (ref "IH1") (pin "1") (pinfunction "1_1") (pintype "passive"))
      (node (ref "IH1") (pin "13") (pinfunction "13_13") (pintype "passive"))
      (node (ref "IH1") (pin "5") (pinfunction "5_5") (pintype "passive"))
      (node (ref "IH1") (pin "9") (pinfunction "9_9") (pintype "passive"))
      (node (ref "IH5") (pin "1") (pinfunction "1_1") (pintype "passive"))
      (node (ref "IH5") (pin "13") (pinfunction "13_13") (pintype "passive"))
      (node (ref "IH5") (pin "5") (pinfunction "5_5") (pintype "passive"))
      (node (ref "IH5") (pin "9") (pinfunction "9_9") (pintype "passive"))
      (node (ref "U4") (pin "15") (pinfunction "~{Y0}_15") (pintype "output"))
    )
    (net (code "36") (name "BC_2") (class "Default")
      (node (ref "IH1") (pin "11") (pinfunction "11_11") (pintype "passive"))
      (node (ref "IH1") (pin "15") (pinfunction "15_15") (pintype "passive"))
      (node (ref "IH1") (pin "3") (pinfunction "3_3") (pintype "passive"))
      (node (ref "IH1") (pin "7") (pinfunction "7_7") (pintype "passive"))
      (node (ref "IH5") (pin "11") (pinfunction "11_11") (pintype "passive"))
      (node (ref "IH5") (pin "15") (pinfunction "15_15") (pintype "passive"))
      (node (ref "IH5") (pin "3") (pinfunction "3_3") (pintype "passive"))
      (node (ref "IH5") (pin "7") (pinfunction "7_7") (pintype "passive"))
      (node (ref "U4") (pin "7") (pinfunction "~{Y7}_7") (pintype "output"))
    )
    (net (code "37") (name "BC_3") (class "Default")
      (node (ref "IH2") (pin "1") (pinfunction "1_1") (pintype "passive"))
      (node (ref "IH2") (pin "13") (pinfunction "13_13") (pintype "passive"))
      (node (ref "IH2") (pin "5") (pinfunction "5_5") (pintype "passive"))
      (node (ref "IH2") (pin "9") (pinfunction "9_9") (pintype "passive"))
      (node (ref "IH6") (pin "1") (pinfunction "1_1") (pintype "passive"))
      (node (ref "IH6") (pin "13") (pinfunction "13_13") (pintype "passive"))
      (node (ref "IH6") (pin "5") (pinfunction "5_5") (pintype "passive"))
      (node (ref "IH6") (pin "9") (pinfunction "9_9") (pintype "passive"))
      (node (ref "U4") (pin "13") (pinfunction "~{Y2}_13") (pintype "output"))
    )
    (net (code "38") (name "BC_4") (class "Default")
      (node (ref "IH2") (pin "11") (pinfunction "11_11") (pintype "passive"))
      (node (ref "IH2") (pin "15") (pinfunction "15_15") (pintype "passive"))
      (node (ref "IH2") (pin "3") (pinfunction "3_3") (pintype "passive"))
      (node (ref "IH2") (pin "7") (pinfunction "7_7") (pintype "passive"))
      (node (ref "IH6") (pin "11") (pinfunction "11_11") (pintype "passive"))
      (node (ref "IH6") (pin "15") (pinfunction "15_15") (pintype "passive"))
      (node (ref "IH6") (pin "3") (pinfunction "3_3") (pintype "passive"))
      (node (ref "IH6") (pin "7") (pinfunction "7_7") (pintype "passive"))
      (node (ref "U4") (pin "14") (pinfunction "~{Y1}_14") (pintype "output"))
    )
    (net (code "39") (name "BC_5") (class "Default")
      (node (ref "IH3") (pin "1") (pinfunction "1_1") (pintype "passive"))
      (node (ref "IH3") (pin "13") (pinfunction "13_13") (pintype "passive"))
      (node (ref "IH3") (pin "5") (pinfunction "5_5") (pintype "passive"))
      (node (ref "IH3") (pin "9") (pinfunction "9_9") (pintype "passive"))
      (node (ref "IH7") (pin "1") (pinfunction "1_1") (pintype "passive"))
      (node (ref "IH7") (pin "13") (pinfunction "13_13") (pintype "passive"))
      (node (ref "IH7") (pin "5") (pinfunction "5_5") (pintype "passive"))
      (node (ref "IH7") (pin "9") (pinfunction "9_9") (pintype "passive"))
      (node (ref "U4") (pin "11") (pinfunction "~{Y4}_11") (pintype "output"))
    )
    (net (code "40") (name "BC_6") (class "Default")
      (node (ref "IH3") (pin "11") (pinfunction "11_11") (pintype "passive"))
      (node (ref "IH3") (pin "15") (pinfunction "15_15") (pintype "passive"))
      (node (ref "IH3") (pin "3") (pinfunction "3_3") (pintype "passive"))
      (node (ref "IH3") (pin "7") (pinfunction "7_7") (pintype "passive"))
      (node (ref "IH7") (pin "11") (pinfunction "11_11") (pintype "passive"))
      (node (ref "IH7") (pin "15") (pinfunction "15_15") (pintype "passive"))
      (node (ref "IH7") (pin "3") (pinfunction "3_3") (pintype "passive"))
      (node (ref "IH7") (pin "7") (pinfunction "7_7") (pintype "passive"))
      (node (ref "U4") (pin "12") (pinfunction "~{Y3}_12") (pintype "output"))
    )
    (net (code "41") (name "BC_7") (class "Default")
      (node (ref "IH4") (pin "1") (pinfunction "1_1") (pintype "passive"))
      (node (ref "IH4") (pin "13") (pinfunction "13_13") (pintype "passive"))
      (node (ref "IH4") (pin "5") (pinfunction "5_5") (pintype "passive"))
      (node (ref "IH4") (pin "9") (pinfunction "9_9") (pintype "passive"))
      (node (ref "IH8") (pin "1") (pinfunction "1_1") (pintype "passive"))
      (node (ref "IH8") (pin "13") (pinfunction "13_13") (pintype "passive"))
      (node (ref "IH8") (pin "5") (pinfunction "5_5") (pintype "passive"))
      (node (ref "IH8") (pin "9") (pinfunction "9_9") (pintype "passive"))
      (node (ref "U4") (pin "10") (pinfunction "~{Y5}_10") (pintype "output"))
    )
    (net (code "42") (name "BC_8") (class "Default")
      (node (ref "IH4") (pin "11") (pinfunction "11_11") (pintype "passive"))
      (node (ref "IH4") (pin "15") (pinfunction "15_15") (pintype "passive"))
      (node (ref "IH4") (pin "3") (pinfunction "3_3") (pintype "passive"))
      (node (ref "IH4") (pin "7") (pinfunction "7_7") (pintype "passive"))
      (node (ref "IH8") (pin "11") (pinfunction "11_11") (pintype "passive"))
      (node (ref "IH8") (pin "15") (pinfunction "15_15") (pintype "passive"))
      (node (ref "IH8") (pin "3") (pinfunction "3_3") (pintype "passive"))
      (node (ref "IH8") (pin "7") (pinfunction "7_7") (pintype "passive"))
      (node (ref "U4") (pin "9") (pinfunction "~{Y6}_9") (pintype "output"))
    )
    (net (code "43") (name "BOOT0") (class "Default")
      (node (ref "R3") (pin "2") (pinfunction "2_2") (pintype "passive"))
      (node (ref "U1") (pin "60") (pinfunction "BOOT0_60") (pintype "bidirectional"))
    )
    (net (code "44") (name "BR_1") (class "Default")
      (node (ref "D1") (pin "3") (pinfunction "3_3") (pintype "passive"))
      (node (ref "D2") (pin "3") (pinfunction "3_3") (pintype "passive"))
      (node (ref "D3") (pin "3") (pinfunction "3_3") (pintype "passive"))
      (node (ref "D4") (pin "3") (pinfunction "3_3") (pintype "passive"))
      (node (ref "R9") (pin "2") (pinfunction "2_2") (pintype "passive"))
      (node (ref "U1") (pin "20") (pinfunction "PA4_20") (pintype "bidirectional"))
    )
    (net (code "45") (name "BR_2") (class "Default")
      (node (ref "D5") (pin "3") (pinfunction "3_3") (pintype "passive"))
      (node (ref "D6") (pin "3") (pinfunction "3_3") (pintype "passive"))
      (node (ref "D7") (pin "3") (pinfunction "3_3") (pintype "passive"))
      (node (ref "D8") (pin "3") (pinfunction "3_3") (pintype "passive"))
      (node (ref "R11") (pin "2") (pinfunction "2_2") (pintype "passive"))
      (node (ref "U1") (pin "21") (pinfunction "PA5_21") (pintype "bidirectional"))
    )
    (net (code "46") (name "BR_3") (class "Default")
      (node (ref "D10") (pin "3") (pinfunction "3_3") (pintype "passive"))
      (node (ref "D11") (pin "3") (pinfunction "3_3") (pintype "passive"))
      (node (ref "D12") (pin "3") (pinfunction "3_3") (pintype "passive"))
      (node (ref "D9") (pin "3") (pinfunction "3_3") (pintype "passive"))
      (node (ref "R13") (pin "2") (pinfunction "2_2") (pintype "passive"))
      (node (ref "U1") (pin "24") (pinfunction "PC4_24") (pintype "bidirectional"))
    )
    (net (code "47") (name "BR_4") (class "Default")
      (node (ref "D13") (pin "3") (pinfunction "3_3") (pintype "passive"))
      (node (ref "D14") (pin "3") (pinfunction "3_3") (pintype "passive"))
      (node (ref "D15") (pin "3") (pinfunction "3_3") (pintype "passive"))
      (node (ref "D16") (pin "3") (pinfunction "3_3") (pintype "passive"))
      (node (ref "R14") (pin "2") (pinfunction "2_2") (pintype "passive"))
      (node (ref "U1") (pin "25") (pinfunction "PC5_25") (pintype "bidirectional"))
    )
    (net (code "48") (name "BR_5") (class "Default")
      (node (ref "D30") (pin "3") (pinfunction "3_3") (pintype "passive"))
      (node (ref "D31") (pin "3") (pinfunction "3_3") (pintype "passive"))
      (node (ref "D32") (pin "3") (pinfunction "3_3") (pintype "passive"))
      (node (ref "D33") (pin "3") (pinfunction "3_3") (pintype "passive"))
      (node (ref "R15") (pin "2") (pinfunction "2_2") (pintype "passive"))
      (node (ref "U1") (pin "30") (pinfunction "PB11_30") (pintype "bidirectional"))
    )
    (net (code "49") (name "BR_6") (class "Default")
      (node (ref "D26") (pin "3") (pinfunction "3_3") (pintype "passive"))
      (node (ref "D27") (pin "3") (pinfunction "3_3") (pintype "passive"))
      (node (ref "D28") (pin "3") (pinfunction "3_3") (pintype "passive"))
      (node (ref "D29") (pin "3") (pinfunction "3_3") (pintype "passive"))
      (node (ref "R16") (pin "2") (pinfunction "2_2") (pintype "passive"))
      (node (ref "U1") (pin "29") (pinfunction "PB10_29") (pintype "bidirectional"))
    )
    (net (code "50") (name "BR_7") (class "Default")
      (node (ref "D22") (pin "3") (pinfunction "3_3") (pintype "passive"))
      (node (ref "D23") (pin "3") (pinfunction "3_3") (pintype "passive"))
      (node (ref "D24") (pin "3") (pinfunction "3_3") (pintype "passive"))
      (node (ref "D25") (pin "3") (pinfunction "3_3") (pintype "passive"))
      (node (ref "R17") (pin "2") (pinfunction "2_2") (pintype "passive"))
      (node (ref "U1") (pin "28") (pinfunction "PB2_28") (pintype "bidirectional"))
    )
    (net (code "51") (name "BR_8") (class "Default")
      (node (ref "D18") (pin "3") (pinfunction "3_3") (pintype "passive"))
      (node (ref "D19") (pin "3") (pinfunction "3_3") (pintype "passive"))
      (node (ref "D20") (pin "3") (pinfunction "3_3") (pintype "passive"))
      (node (ref "D21") (pin "3") (pinfunction "3_3") (pintype "passive"))
      (node (ref "R18") (pin "2") (pinfunction "2_2") (pintype "passive"))
      (node (ref "U1") (pin "27") (pinfunction "PB1_27") (pintype "bidirectional"))
    )
    (net (code "52") (name "BTLDR_BUTTON") (class "Default")
      (node (ref "CONN2") (pin "1") (pinfunction "1_1") (pintype "passive"))
      (node (ref "U1") (pin "56") (pinfunction "PB4_56") (pintype "bidirectional"))
    )
    (net (code "53") (name "D+") (class "Default")
      (node (ref "R1") (pin "2") (pinfunction "2_2") (pintype "passive"))
      (node (ref "U1") (pin "45") (pinfunction "PA12_45") (pintype "bidirectional"))
    )
    (net (code "54") (name "D+X") (class "Default")
      (node (ref "CONN1") (pin "D+") (pinfunction "D+_D+") (pintype "bidirectional"))
      (node (ref "D17") (pin "3") (pinfunction "I/O2_3") (pintype "passive"))
      (node (ref "R1") (pin "1") (pinfunction "1_1") (pintype "passive"))
    )
    (net (code "55") (name "D-") (class "Default")
      (node (ref "R2") (pin "1") (pinfunction "1_1") (pintype "passive"))
      (node (ref "U1") (pin "44") (pinfunction "PA11_44") (pintype "bidirectional"))
    )
    (net (code "56") (name "D-X") (class "Default")
      (node (ref "CONN1") (pin "D-") (pinfunction "D-_D-") (pintype "bidirectional"))
      (node (ref "D17") (pin "2") (pinfunction "I/O1_2") (pintype "passive"))
      (node (ref "R2") (pin "2") (pinfunction "2_2") (pintype "passive"))
    )
    (net (code "57") (name "DEC_DI_A0") (class "Default")
      (node (ref "U1") (pin "39") (pinfunction "PC8_39") (pintype "bidirectional"))
      (node (ref "U4") (pin "1") (pinfunction "A0_1") (pintype "input"))
    )
    (net (code "58") (name "DEC_DI_A1") (class "Default")
      (node (ref "U1") (pin "40") (pinfunction "PC9_40") (pintype "bidirectional"))
      (node (ref "U4") (pin "2") (pinfunction "A1_2") (pintype "input"))
    )
    (net (code "59") (name "DEC_DI_A2") (class "Default")
      (node (ref "U1") (pin "41") (pinfunction "PA8_41") (pintype "bidirectional"))
      (node (ref "U4") (pin "3") (pinfunction "A2_3") (pintype "input"))
    )
    (net (code "60") (name "DEC_DO_A0") (class "Default")
      (node (ref "U1") (pin "16") (pinfunction "PA2_16") (pintype "bidirectional"))
      (node (ref "U7") (pin "2") (pinfunction "1A_2") (pintype "bidirectional"))
    )
    (net (code "61") (name "DEC_DO_A1") (class "Default")
      (node (ref "U1") (pin "15") (pinfunction "PA1_15") (pintype "bidirectional"))
      (node (ref "U7") (pin "5") (pinfunction "2A_5") (pintype "bidirectional"))
    )
    (net (code "62") (name "DEC_DO_A2") (class "Default")
      (node (ref "U1") (pin "14") (pinfunction "PA0_14") (pintype "bidirectional"))
      (node (ref "U7") (pin "9") (pinfunction "3A_9") (pintype "bidirectional"))
    )
    (net (code "63") (name "GND") (class "Default")
      (node (ref "AH1") (pin "1") (pinfunction "1_1") (pintype "passive"))
      (node (ref "AH1") (pin "10") (pinfunction "4_10") (pintype "passive"))
      (node (ref "AH1") (pin "13") (pinfunction "5_13") (pintype "passive"))
      (node (ref "AH1") (pin "16") (pinfunction "6_16") (pintype "passive"))
      (node (ref "AH1") (pin "19") (pinfunction "7_19") (pintype "passive"))
      (node (ref "AH1") (pin "22") (pinfunction "8_22") (pintype "passive"))
      (node (ref "AH1") (pin "4") (pinfunction "2_4") (pintype "passive"))
      (node (ref "AH1") (pin "7") (pinfunction "3_7") (pintype "passive"))
      (node (ref "AH2") (pin "1") (pinfunction "1_1") (pintype "passive"))
      (node (ref "AH2") (pin "10") (pinfunction "4_10") (pintype "passive"))
      (node (ref "AH2") (pin "13") (pinfunction "5_13") (pintype "passive"))
      (node (ref "AH2") (pin "16") (pinfunction "6_16") (pintype "passive"))
      (node (ref "AH2") (pin "19") (pinfunction "7_19") (pintype "passive"))
      (node (ref "AH2") (pin "22") (pinfunction "8_22") (pintype "passive"))
      (node (ref "AH2") (pin "4") (pinfunction "2_4") (pintype "passive"))
      (node (ref "AH2") (pin "7") (pinfunction "3_7") (pintype "passive"))
      (node (ref "AH3") (pin "1") (pinfunction "1_1") (pintype "passive"))
      (node (ref "AH3") (pin "10") (pinfunction "4_10") (pintype "passive"))
      (node (ref "AH3") (pin "13") (pinfunction "5_13") (pintype "passive"))
      (node (ref "AH3") (pin "16") (pinfunction "6_16") (pintype "passive"))
      (node (ref "AH3") (pin "19") (pinfunction "7_19") (pintype "passive"))
      (node (ref "AH3") (pin "22") (pinfunction "8_22") (pintype "passive"))
      (node (ref "AH3") (pin "4") (pinfunction "2_4") (pintype "passive"))
      (node (ref "AH3") (pin "7") (pinfunction "3_7") (pintype "passive"))
      (node (ref "AH4") (pin "1") (pinfunction "1_1") (pintype "passive"))
      (node (ref "AH4") (pin "10") (pinfunction "4_10") (pintype "passive"))
      (node (ref "AH4") (pin "13") (pinfunction "5_13") (pintype "passive"))
      (node (ref "AH4") (pin "16") (pinfunction "6_16") (pintype "passive"))
      (node (ref "AH4") (pin "19") (pinfunction "7_19") (pintype "passive"))
      (node (ref "AH4") (pin "22") (pinfunction "8_22") (pintype "passive"))
      (node (ref "AH4") (pin "4") (pinfunction "2_4") (pintype "passive"))
      (node (ref "AH4") (pin "7") (pinfunction "3_7") (pintype "passive"))
      (node (ref "C1") (pin "1") (pinfunction "1_1") (pintype "passive"))
      (node (ref "C10") (pin "2") (pinfunction "2_2") (pintype "passive"))
      (node (ref "C11") (pin "2") (pinfunction "2_2") (pintype "passive"))
      (node (ref "C15") (pin "1") (pinfunction "1_1") (pintype "passive"))
      (node (ref "C16") (pin "2") (pinfunction "2_2") (pintype "passive"))
      (node (ref "C17") (pin "2") (pinfunction "2_2") (pintype "passive"))
      (node (ref "C18") (pin "1") (pinfunction "1_1") (pintype "passive"))
      (node (ref "C19") (pin "1") (pinfunction "1_1") (pintype "passive"))
      (node (ref "C2") (pin "2") (pinfunction "2_2") (pintype "passive"))
      (node (ref "C20") (pin "1") (pinfunction "1_1") (pintype "passive"))
      (node (ref "C21") (pin "2") (pinfunction "2_2") (pintype "passive"))
      (node (ref "C22") (pin "2") (pinfunction "2_2") (pintype "passive"))
      (node (ref "C23") (pin "2") (pinfunction "2_2") (pintype "passive"))
      (node (ref "C24") (pin "2") (pinfunction "2_2") (pintype "passive"))
      (node (ref "C3") (pin "2") (pinfunction "2_2") (pintype "passive"))
      (node (ref "C4") (pin "1") (pinfunction "1_1") (pintype "passive"))
      (node (ref "C5") (pin "2") (pinfunction "2_2") (pintype "passive"))
      (node (ref "C6") (pin "1") (pinfunction "1_1") (pintype "passive"))
      (node (ref "C7") (pin "2") (pinfunction "2_2") (pintype "passive"))
      (node (ref "C8") (pin "2") (pinfunction "2_2") (pintype "passive"))
      (node (ref "C9") (pin "2") (pinfunction "2_2") (pintype "passive"))
      (node (ref "CONN1") (pin "GND") (pinfunction "GND_GND") (pintype "bidirectional"))
      (node (ref "CONN2") (pin "2") (pinfunction "2_2") (pintype "passive"))
      (node (ref "CONN4") (pin "2") (pinfunction "2_2") (pintype "passive"))
      (node (ref "CONN6") (pin "3") (pinfunction "3_3") (pintype "passive"))
      (node (ref "CONN7") (pin "3") (pinfunction "3_3") (pintype "passive"))
      (node (ref "CONN8") (pin "2") (pinfunction "2_2") (pintype "passive"))
      (node (ref "D17") (pin "1") (pinfunction "GND_1") (pintype "passive"))
      (node (ref "D35") (pin "C") (pinfunction "C_C") (pintype "passive"))
      (node (ref "D36") (pin "C") (pinfunction "C_C") (pintype "passive"))
      (node (ref "D37") (pin "C") (pinfunction "C_C") (pintype "passive"))
      (node (ref "L1") (pin "1") (pinfunction "1_1") (pintype "passive"))
      (node (ref "R3") (pin "1") (pinfunction "1_1") (pintype "passive"))
      (node (ref "U1") (pin "12") (pinfunction "VSSA_12") (pintype "bidirectional"))
      (node (ref "U1") (pin "18") (pinfunction "VSS_18") (pintype "bidirectional"))
      (node (ref "U1") (pin "63") (pinfunction "VSS_63") (pintype "bidirectional"))
      (node (ref "U2") (pin "5") (pinfunction "GND_5") (pintype "power_in"))
      (node (ref "U3") (pin "4") (pinfunction "GND_4") (pintype "power_in"))
      (node (ref "U3") (pin "9") (pinfunction "GND_9") (pintype "power_in"))
      (node (ref "U4") (pin "4") (pinfunction "~{E1}_4") (pintype "input"))
      (node (ref "U4") (pin "5") (pinfunction "~{E2}_5") (pintype "input"))
      (node (ref "U4") (pin "8") (pinfunction "GND_8") (pintype "power_in"))
      (node (ref "U5") (pin "12") (pinfunction "GND_12") (pintype "passive"))
      (node (ref "U5") (pin "15") (pinfunction "~{E}_15") (pintype "input"))
      (node (ref "U6") (pin "12") (pinfunction "GND_12") (pintype "passive"))
      (node (ref "U6") (pin "15") (pinfunction "~{E}_15") (pintype "input"))
      (node (ref "U7") (pin "1") (pinfunction "1~{(OE})_1") (pintype "bidirectional"))
      (node (ref "U7") (pin "10") (pinfunction "3~{(OE})_10") (pintype "bidirectional"))
      (node (ref "U7") (pin "4") (pinfunction "2~{(OE})_4") (pintype "bidirectional"))
      (node (ref "U7") (pin "7") (pinfunction "VEE_7") (pintype "passive"))
      (node (ref "VR2") (pin "2") (pinfunction "GND_2") (pintype "passive"))
      (node (ref "Y1") (pin "2") (pinfunction "VEE_2") (pintype "passive"))
      (node (ref "Y1") (pin "4") (pinfunction "VEE_4") (pintype "passive"))
    )
    (net (code "64") (name "LC_1") (class "Default")
      (node (ref "OH1") (pin "10") (pinfunction "10_10") (pintype "passive"))
      (node (ref "OH1") (pin "12") (pinfunction "12_12") (pintype "passive"))
      (node (ref "OH1") (pin "2") (pinfunction "2_2") (pintype "passive"))
      (node (ref "OH1") (pin "4") (pinfunction "4_4") (pintype "passive"))
      (node (ref "OH1") (pin "6") (pinfunction "6_6") (pintype "passive"))
      (node (ref "OH1") (pin "8") (pinfunction "8_8") (pintype "passive"))
      (node (ref "U3") (pin "2") (pinfunction "DIG_0_2") (pintype "output"))
    )
    (net (code "65") (name "LC_2") (class "Default")
      (node (ref "OH2") (pin "10") (pinfunction "10_10") (pintype "passive"))
      (node (ref "OH2") (pin "12") (pinfunction "12_12") (pintype "passive"))
      (node (ref "OH2") (pin "2") (pinfunction "2_2") (pintype "passive"))
      (node (ref "OH2") (pin "4") (pinfunction "4_4") (pintype "passive"))
      (node (ref "OH2") (pin "6") (pinfunction "6_6") (pintype "passive"))
      (node (ref "OH2") (pin "8") (pinfunction "8_8") (pintype "passive"))
      (node (ref "U3") (pin "3") (pinfunction "DIG_4_3") (pintype "output"))
    )
    (net (code "66") (name "LC_3") (class "Default")
      (node (ref "OH3") (pin "10") (pinfunction "10_10") (pintype "passive"))
      (node (ref "OH3") (pin "12") (pinfunction "12_12") (pintype "passive"))
      (node (ref "OH3") (pin "2") (pinfunction "2_2") (pintype "passive"))
      (node (ref "OH3") (pin "4") (pinfunction "4_4") (pintype "passive"))
      (node (ref "OH3") (pin "6") (pinfunction "6_6") (pintype "passive"))
      (node (ref "OH3") (pin "8") (pinfunction "8_8") (pintype "passive"))
      (node (ref "U3") (pin "5") (pinfunction "DIG_6_5") (pintype "output"))
    )
    (net (code "67") (name "LC_4") (class "Default")
      (node (ref "OH4") (pin "10") (pinfunction "10_10") (pintype "passive"))
      (node (ref "OH4") (pin "12") (pinfunction "12_12") (pintype "passive"))
      (node (ref "OH4") (pin "2") (pinfunction "2_2") (pintype "passive"))
      (node (ref "OH4") (pin "4") (pinfunction "4_4") (pintype "passive"))
      (node (ref "OH4") (pin "6") (pinfunction "6_6") (pintype "passive"))
      (node (ref "OH4") (pin "8") (pinfunction "8_8") (pintype "passive"))
      (node (ref "U3") (pin "6") (pinfunction "DIG_2_6") (pintype "output"))
    )
    (net (code "68") (name "LC_5") (class "Default")
      (node (ref "OH5") (pin "10") (pinfunction "10_10") (pintype "passive"))
      (node (ref "OH5") (pin "12") (pinfunction "12_12") (pintype "passive"))
      (node (ref "OH5") (pin "2") (pinfunction "2_2") (pintype "passive"))
      (node (ref "OH5") (pin "4") (pinfunction "4_4") (pintype "passive"))
      (node (ref "OH5") (pin "6") (pinfunction "6_6") (pintype "passive"))
      (node (ref "OH5") (pin "8") (pinfunction "8_8") (pintype "passive"))
      (node (ref "U3") (pin "7") (pinfunction "DIG_3_7") (pintype "output"))
    )
    (net (code "69") (name "LC_6") (class "Default")
      (node (ref "OH6") (pin "10") (pinfunction "10_10") (pintype "passive"))
      (node (ref "OH6") (pin "12") (pinfunction "12_12") (pintype "passive"))
      (node (ref "OH6") (pin "2") (pinfunction "2_2") (pintype "passive"))
      (node (ref "OH6") (pin "4") (pinfunction "4_4") (pintype "passive"))
      (node (ref "OH6") (pin "6") (pinfunction "6_6") (pintype "passive"))
      (node (ref "OH6") (pin "8") (pinfunction "8_8") (pintype "passive"))
      (node (ref "U3") (pin "8") (pinfunction "DIG_7_8") (pintype "output"))
    )
    (net (code "70") (name "LC_7") (class "Default")
      (node (ref "OH7") (pin "10") (pinfunction "10_10") (pintype "passive"))
      (node (ref "OH7") (pin "12") (pinfunction "12_12") (pintype "passive"))
      (node (ref "OH7") (pin "2") (pinfunction "2_2") (pintype "passive"))
      (node (ref "OH7") (pin "4") (pinfunction "4_4") (pintype "passive"))
      (node (ref "OH7") (pin "6") (pinfunction "6_6") (pintype "passive"))
      (node (ref "OH7") (pin "8") (pinfunction "8_8") (pintype "passive"))
      (node (ref "U3") (pin "10") (pinfunction "DIG_5_10") (pintype "output"))
    )
    (net (code "71") (name "LC_8") (class "Default")
      (node (ref "OH8") (pin "10") (pinfunction "10_10") (pintype "passive"))
      (node (ref "OH8") (pin "12") (pinfunction "12_12") (pintype "passive"))
      (node (ref "OH8") (pin "2") (pinfunction "2_2") (pintype "passive"))
      (node (ref "OH8") (pin "4") (pinfunction "4_4") (pintype "passive"))
      (node (ref "OH8") (pin "6") (pinfunction "6_6") (pintype "passive"))
      (node (ref "OH8") (pin "8") (pinfunction "8_8") (pintype "passive"))
      (node (ref "U3") (pin "11") (pinfunction "DIG_1_11") (pintype "output"))
    )
    (net (code "72") (name "LR_1_MI") (class "Default")
      (node (ref "U1") (pin "62") (pinfunction "PB9_62") (pintype "bidirectional"))
    )
    (net (code "73") (name "LR_1_MO") (class "Default")
      (node (ref "OH1") (pin "1") (pinfunction "1_1") (pintype "passive"))
      (node (ref "OH2") (pin "1") (pinfunction "1_1") (pintype "passive"))
      (node (ref "OH3") (pin "1") (pinfunction "1_1") (pintype "passive"))
      (node (ref "OH4") (pin "1") (pinfunction "1_1") (pintype "passive"))
      (node (ref "OH5") (pin "1") (pinfunction "1_1") (pintype "passive"))
      (node (ref "OH6") (pin "1") (pinfunction "1_1") (pintype "passive"))
      (node (ref "OH7") (pin "1") (pinfunction "1_1") (pintype "passive"))
      (node (ref "OH8") (pin "1") (pinfunction "1_1") (pintype "passive"))
      (node (ref "U3") (pin "23") (pinfunction "SEG_D_23") (pintype "output"))
    )
    (net (code "74") (name "LR_2_MI") (class "Default")
      (node (ref "U1") (pin "61") (pinfunction "PB8_61") (pintype "bidirectional"))
    )
    (net (code "75") (name "LR_2_MO") (class "Default")
      (node (ref "OH1") (pin "3") (pinfunction "3_3") (pintype "passive"))
      (node (ref "OH2") (pin "3") (pinfunction "3_3") (pintype "passive"))
      (node (ref "OH3") (pin "3") (pinfunction "3_3") (pintype "passive"))
      (node (ref "OH4") (pin "3") (pinfunction "3_3") (pintype "passive"))
      (node (ref "OH5") (pin "3") (pinfunction "3_3") (pintype "passive"))
      (node (ref "OH6") (pin "3") (pinfunction "3_3") (pintype "passive"))
      (node (ref "OH7") (pin "3") (pinfunction "3_3") (pintype "passive"))
      (node (ref "OH8") (pin "3") (pinfunction "3_3") (pintype "passive"))
      (node (ref "U3") (pin "22") (pinfunction "SEG_DP_22") (pintype "output"))
    )
    (net (code "76") (name "LR_3_MI") (class "Default")
      (node (ref "U1") (pin "17") (pinfunction "PA3_17") (pintype "bidirectional"))
    )
    (net (code "77") (name "LR_3_MO") (class "Default")
      (node (ref "OH1") (pin "9") (pinfunction "9_9") (pintype "passive"))
      (node (ref "OH2") (pin "9") (pinfunction "9_9") (pintype "passive"))
      (node (ref "OH3") (pin "9") (pinfunction "9_9") (pintype "passive"))
      (node (ref "OH4") (pin "9") (pinfunction "9_9") (pintype "passive"))
      (node (ref "OH5") (pin "9") (pinfunction "9_9") (pintype "passive"))
      (node (ref "OH6") (pin "9") (pinfunction "9_9") (pintype "passive"))
      (node (ref "OH7") (pin "9") (pinfunction "9_9") (pintype "passive"))
      (node (ref "OH8") (pin "9") (pinfunction "9_9") (pintype "passive"))
      (node (ref "U3") (pin "17") (pinfunction "SEG_G_17") (pintype "output"))
    )
    (net (code "78") (name "LR_4_MI") (class "Default")
      (node (ref "U1") (pin "22") (pinfunction "PA6_22") (pintype "bidirectional"))
    )
    (net (code "79") (name "LR_4_MO") (class "Default")
      (node (ref "OH1") (pin "11") (pinfunction "11_11") (pintype "passive"))
      (node (ref "OH2") (pin "11") (pinfunction "11_11") (pintype "passive"))
      (node (ref "OH3") (pin "11") (pinfunction "11_11") (pintype "passive"))
      (node (ref "OH4") (pin "11") (pinfunction "11_11") (pintype "passive"))
      (node (ref "OH5") (pin "11") (pinfunction "11_11") (pintype "passive"))
      (node (ref "OH6") (pin "11") (pinfunction "11_11") (pintype "passive"))
      (node (ref "OH7") (pin "11") (pinfunction "11_11") (pintype "passive"))
      (node (ref "OH8") (pin "11") (pinfunction "11_11") (pintype "passive"))
      (node (ref "U3") (pin "16") (pinfunction "SEG_B_16") (pintype "output"))
    )
    (net (code "80") (name "LR_5_MI") (class "Default")
      (node (ref "U1") (pin "23") (pinfunction "PA7_23") (pintype "bidirectional"))
    )
    (net (code "81") (name "LR_5_MO") (class "Default")
      (node (ref "OH1") (pin "5") (pinfunction "5_5") (pintype "passive"))
      (node (ref "OH2") (pin "5") (pinfunction "5_5") (pintype "passive"))
      (node (ref "OH3") (pin "5") (pinfunction "5_5") (pintype "passive"))
      (node (ref "OH4") (pin "5") (pinfunction "5_5") (pintype "passive"))
      (node (ref "OH5") (pin "5") (pinfunction "5_5") (pintype "passive"))
      (node (ref "OH6") (pin "5") (pinfunction "5_5") (pintype "passive"))
      (node (ref "OH7") (pin "5") (pinfunction "5_5") (pintype "passive"))
      (node (ref "OH8") (pin "5") (pinfunction "5_5") (pintype "passive"))
      (node (ref "U3") (pin "21") (pinfunction "SEG_E_21") (pintype "output"))
    )
    (net (code "82") (name "LR_6_MI") (class "Default")
      (node (ref "U1") (pin "26") (pinfunction "PB0_26") (pintype "bidirectional"))
    )
    (net (code "83") (name "LR_6_MO") (class "Default")
      (node (ref "OH1") (pin "7") (pinfunction "7_7") (pintype "passive"))
      (node (ref "OH2") (pin "7") (pinfunction "7_7") (pintype "passive"))
      (node (ref "OH3") (pin "7") (pinfunction "7_7") (pintype "passive"))
      (node (ref "OH4") (pin "7") (pinfunction "7_7") (pintype "passive"))
      (node (ref "OH5") (pin "7") (pinfunction "7_7") (pintype "passive"))
      (node (ref "OH6") (pin "7") (pinfunction "7_7") (pintype "passive"))
      (node (ref "OH7") (pin "7") (pinfunction "7_7") (pintype "passive"))
      (node (ref "OH8") (pin "7") (pinfunction "7_7") (pintype "passive"))
      (node (ref "U3") (pin "20") (pinfunction "SEG_C_20") (pintype "output"))
    )
    (net (code "84") (name "MIDI_IN") (class "Default")
      (node (ref "R4") (pin "2") (pinfunction "2_2") (pintype "passive"))
      (node (ref "U1") (pin "38") (pinfunction "PC7_38") (pintype "bidirectional"))
      (node (ref "U2") (pin "6") (pinfunction "VO_6") (pintype "output"))
    )
    (net (code "85") (name "MIDI_IN_LED") (class "Default")
      (node (ref "R7") (pin "2") (pinfunction "2_2") (pintype "passive"))
      (node (ref "U1") (pin "43") (pinfunction "PA10_43") (pintype "bidirectional"))
    )
    (net (code "86") (name "MIDI_OUT") (class "Default")
      (node (ref "R12") (pin "2") (pinfunction "2_2") (pintype "passive"))
      (node (ref "U1") (pin "37") (pinfunction "PC6_37") (pintype "bidirectional"))
    )
    (net (code "87") (name "MIDI_OUT_LED") (class "Default")
      (node (ref "R6") (pin "2") (pinfunction "2_2") (pintype "passive"))
      (node (ref "U1") (pin "42") (pinfunction "PA9_42") (pintype "bidirectional"))
    )
    (net (code "88") (name "MUX_COMMON_1") (class "Default")
      (node (ref "U1") (pin "10") (pinfunction "PC2_10") (pintype "bidirectional"))
      (node (ref "U5") (pin "1") (pinfunction "Z_1") (pintype "bidirectional"))
    )
    (net (code "89") (name "MUX_COMMON_2") (class "Default")
      (node (ref "U1") (pin "9") (pinfunction "PC1_9") (pintype "bidirectional"))
      (node (ref "U6") (pin "1") (pinfunction "Z_1") (pintype "bidirectional"))
    )
    (net (code "90") (name "MUX_S0") (class "Default")
      (node (ref "U1") (pin "35") (pinfunction "PB14_35") (pintype "bidirectional"))
      (node (ref "U5") (pin "10") (pinfunction "S0_10") (pintype "input"))
      (node (ref "U6") (pin "10") (pinfunction "S0_10") (pintype "input"))
    )
    (net (code "91") (name "MUX_S1") (class "Default")
      (node (ref "U1") (pin "36") (pinfunction "PB15_36") (pintype "bidirectional"))
      (node (ref "U5") (pin "11") (pinfunction "S1_11") (pintype "input"))
      (node (ref "U6") (pin "11") (pinfunction "S1_11") (pintype "input"))
    )
    (net (code "92") (name "MUX_S2") (class "Default")
      (node (ref "U1") (pin "33") (pinfunction "PB12_33") (pintype "bidirectional"))
      (node (ref "U5") (pin "14") (pinfunction "S2_14") (pintype "input"))
      (node (ref "U6") (pin "14") (pinfunction "S2_14") (pintype "input"))
    )
    (net (code "93") (name "MUX_S3") (class "Default")
      (node (ref "U1") (pin "34") (pinfunction "PB13_34") (pintype "bidirectional"))
      (node (ref "U5") (pin "13") (pinfunction "S3_13") (pintype "input"))
      (node (ref "U6") (pin "13") (pinfunction "S3_13") (pintype "input"))
    )
    (net (code "94") (name "NRST") (class "Default")
      (node (ref "C17") (pin "1") (pinfunction "1_1") (pintype "passive"))
      (node (ref "U1") (pin "7") (pinfunction "NRST_7") (pintype "bidirectional"))
    )
    (net (code "95") (name "Net-(C1-Pad2)") (class "Default")
      (node (ref "C1") (pin "2") (pinfunction "2_2") (pintype "passive"))
      (node (ref "U1") (pin "31") (pinfunction "VCAP_31") (pintype "bidirectional"))
    )
    (net (code "96") (name "Net-(C2-Pad1)") (class "Default")
      (node (ref "C2") (pin "1") (pinfunction "1_1") (pintype "passive"))
      (node (ref "U1") (pin "47") (pinfunction "VCAP_47") (pintype "bidirectional"))
    )
    (net (code "97") (name "Net-(CONN3-Pad4)") (class "Default")
      (node (ref "CONN3") (pin "4") (pinfunction "4_4") (pintype "bidirectional"))
      (node (ref "R5") (pin "1") (pinfunction "1_1") (pintype "passive"))
    )
    (net (code "98") (name "Net-(CONN4-Pad4)") (class "Default")
      (node (ref "CONN4") (pin "4") (pinfunction "4_4") (pintype "bidirectional"))
      (node (ref "R10") (pin "1") (pinfunction "1_1") (pintype "passive"))
    )
    (net (code "99") (name "Net-(CONN4-Pad5)") (class "Default")
      (node (ref "CONN4") (pin "5") (pinfunction "5_5") (pintype "bidirectional"))
      (node (ref "R12") (pin "1") (pinfunction "1_1") (pintype "passive"))
    )
    (net (code "100") (name "Net-(D1-Pad1)") (class "Default")
      (node (ref "D1") (pin "1") (pinfunction "1_1") (pintype "passive"))
      (node (ref "IH1") (pin "2") (pinfunction "2_2") (pintype "passive"))
    )
    (net (code "101") (name "Net-(D1-Pad2)") (class "Default")
      (node (ref "D1") (pin "2") (pinfunction "2_2") (pintype "passive"))
      (node (ref "IH1") (pin "8") (pinfunction "8_8") (pintype "passive"))
    )
    (net (code "102") (name "Net-(D2-Pad1)") (class "Default")
      (node (ref "D2") (pin "1") (pinfunction "1_1") (pintype "passive"))
      (node (ref "IH2") (pin "2") (pinfunction "2_2") (pintype "passive"))
    )
    (net (code "103") (name "Net-(D2-Pad2)") (class "Default")
      (node (ref "D2") (pin "2") (pinfunction "2_2") (pintype "passive"))
      (node (ref "IH2") (pin "8") (pinfunction "8_8") (pintype "passive"))
    )
    (net (code "104") (name "Net-(D3-Pad1)") (class "Default")
      (node (ref "D3") (pin "1") (pinfunction "1_1") (pintype "passive"))
      (node (ref "IH3") (pin "2") (pinfunction "2_2") (pintype "passive"))
    )
    (net (code "105") (name "Net-(D3-Pad2)") (class "Default")
      (node (ref "D3") (pin "2") (pinfunction "2_2") (pintype "passive"))
      (node (ref "IH3") (pin "8") (pinfunction "8_8") (pintype "passive"))
    )
    (net (code "106") (name "Net-(D4-Pad1)") (class "Default")
      (node (ref "D4") (pin "1") (pinfunction "1_1") (pintype "passive"))
      (node (ref "IH4") (pin "2") (pinfunction "2_2") (pintype "passive"))
    )
    (net (code "107") (name "Net-(D4-Pad2)") (class "Default")
      (node (ref "D4") (pin "2") (pinfunction "2_2") (pintype "passive"))
      (node (ref "IH4") (pin "8") (pinfunction "8_8") (pintype "passive"))
    )
    (net (code "108") (name "Net-(D5-Pad1)") (class "Default")
      (node (ref "D5") (pin "1") (pinfunction "1_1") (pintype "passive"))
      (node (ref "IH1") (pin "4") (pinfunction "4_4") (pintype "passive"))
    )
    (net (code "109") (name "Net-(D5-Pad2)") (class "Default")
      (node (ref "D5") (pin "2") (pinfunction "2_2") (pintype "passive"))
      (node (ref "IH1") (pin "6") (pinfunction "6_6") (pintype "passive"))
    )
    (net (code "110") (name "Net-(D6-Pad1)") (class "Default")
      (node (ref "D6") (pin "1") (pinfunction "1_1") (pintype "passive"))
      (node (ref "IH2") (pin "4") (pinfunction "4_4") (pintype "passive"))
    )
    (net (code "111") (name "Net-(D6-Pad2)") (class "Default")
      (node (ref "D6") (pin "2") (pinfunction "2_2") (pintype "passive"))
      (node (ref "IH2") (pin "6") (pinfunction "6_6") (pintype "passive"))
    )
    (net (code "112") (name "Net-(D7-Pad1)") (class "Default")
      (node (ref "D7") (pin "1") (pinfunction "1_1") (pintype "passive"))
      (node (ref "IH3") (pin "4") (pinfunction "4_4") (pintype "passive"))
    )
    (net (code "113") (name "Net-(D7-Pad2)") (class "Default")
      (node (ref "D7") (pin "2") (pinfunction "2_2") (pintype "passive"))
      (node (ref "IH3") (pin "6") (pinfunction "6_6") (pintype "passive"))
    )
    (net (code "114") (name "Net-(D8-Pad1)") (class "Default")
      (node (ref "D8") (pin "1") (pinfunction "1_1") (pintype "passive"))
      (node (ref "IH4") (pin "4") (pinfunction "4_4") (pintype "passive"))
    )
    (net (code "115") (name "Net-(D8-Pad2)") (class "Default")
      (node (ref "D8") (pin "2") (pinfunction "2_2") (pintype "passive"))
      (node (ref "IH4") (pin "6") (pinfunction "6_6") (pintype "passive"))
    )
    (net (code "116") (name "Net-(D9-Pad1)") (class "Default")
      (node (ref "D9") (pin "1") (pinfunction "1_1") (pintype "passive"))
      (node (ref "IH1") (pin "10") (pinfunction "10_10") (pintype "passive"))
    )
    (net (code "117") (name "Net-(D9-Pad2)") (class "Default")
      (node (ref "D9") (pin "2") (pinfunction "2_2") (pintype "passive"))
      (node (ref "IH1") (pin "16") (pinfunction "16_16") (pintype "passive"))
    )
    (net (code "118") (name "Net-(D10-Pad1)") (class "Default")
      (node (ref "D10") (pin "1") (pinfunction "1_1") (pintype "passive"))
      (node (ref "IH2") (pin "10") (pinfunction "10_10") (pintype "passive"))
    )
    (net (code "119") (name "Net-(D10-Pad2)") (class "Default")
      (node (ref "D10") (pin "2") (pinfunction "2_2") (pintype "passive"))
      (node (ref "IH2") (pin "16") (pinfunction "16_16") (pintype "passive"))
    )
    (net (code "120") (name "Net-(D11-Pad1)") (class "Default")
      (node (ref "D11") (pin "1") (pinfunction "1_1") (pintype "passive"))
      (node (ref "IH3") (pin "10") (pinfunction "10_10") (pintype "passive"))
    )
    (net (code "121") (name "Net-(D11-Pad2)") (class "Default")
      (node (ref "D11") (pin "2") (pinfunction "2_2") (pintype "passive"))
      (node (ref "IH3") (pin "16") (pinfunction "16_16") (pintype "passive"))
    )
    (net (code "122") (name "Net-(D12-Pad1)") (class "Default")
      (node (ref "D12") (pin "1") (pinfunction "1_1") (pintype "passive"))
      (node (ref "IH4") (pin "10") (pinfunction "10_10") (pintype "passive"))
    )
    (net (code "123") (name "Net-(D12-Pad2)") (class "Default")
      (node (ref "D12") (pin "2") (pinfunction "2_2") (pintype "passive"))
      (node (ref "IH4") (pin "16") (pinfunction "16_16") (pintype "passive"))
    )
    (net (code "124") (name "Net-(D13-Pad1)") (class "Default")
      (node (ref "D13") (pin "1") (pinfunction "1_1") (pintype "passive"))
      (node (ref "IH1") (pin "12") (pinfunction "12_12") (pintype "passive"))
    )
    (net (code "125") (name "Net-(D13-Pad2)") (class "Default")
      (node (ref "D13") (pin "2") (pinfunction "2_2") (pintype "passive"))
      (node (ref "IH1") (pin "14") (pinfunction "14_14") (pintype "passive"))
    )
    (net (code "126") (name "Net-(D14-Pad1)") (class "Default")
      (node (ref "D14") (pin "1") (pinfunction "1_1") (pintype "passive"))
      (node (ref "IH2") (pin "12") (pinfunction "12_12") (pintype "passive"))
    )
    (net (code "127") (name "Net-(D14-Pad2)") (class "Default")
      (node (ref "D14") (pin "2") (pinfunction "2_2") (pintype "passive"))
      (node (ref "IH2") (pin "14") (pinfunction "14_14") (pintype "passive"))
    )
    (net (code "128") (name "Net-(D15-Pad1)") (class "Default")
      (node (ref "D15") (pin "1") (pinfunction "1_1") (pintype "passive"))
      (node (ref "IH3") (pin "12") (pinfunction "12_12") (pintype "passive"))
    )
    (net (code "129") (name "Net-(D15-Pad2)") (class "Default")
      (node (ref "D15") (pin "2") (pinfunction "2_2") (pintype "passive"))
      (node (ref "IH3") (pin "14") (pinfunction "14_14") (pintype "passive"))
    )
    (net (code "130") (name "Net-(D16-Pad1)") (class "Default")
      (node (ref "D16") (pin "1") (pinfunction "1_1") (pintype "passive"))
      (node (ref "IH4") (pin "12") (pinfunction "12_12") (pintype "passive"))
    )
    (net (code "131") (name "Net-(D16-Pad2)") (class "Default")
      (node (ref "D16") (pin "2") (pinfunction "2_2") (pintype "passive"))
      (node (ref "IH4") (pin "14") (pinfunction "14_14") (pintype "passive"))
    )
    (net (code "132") (name "Net-(D18-Pad1)") (class "Default")
      (node (ref "D18") (pin "1") (pinfunction "1_1") (pintype "passive"))
      (node (ref "IH5") (pin "2") (pinfunction "2_2") (pintype "passive"))
    )
    (net (code "133") (name "Net-(D18-Pad2)") (class "Default")
      (node (ref "D18") (pin "2") (pinfunction "2_2") (pintype "passive"))
      (node (ref "IH5") (pin "8") (pinfunction "8_8") (pintype "passive"))
    )
    (net (code "134") (name "Net-(D19-Pad1)") (class "Default")
      (node (ref "D19") (pin "1") (pinfunction "1_1") (pintype "passive"))
      (node (ref "IH6") (pin "2") (pinfunction "2_2") (pintype "passive"))
    )
    (net (code "135") (name "Net-(D19-Pad2)") (class "Default")
      (node (ref "D19") (pin "2") (pinfunction "2_2") (pintype "passive"))
      (node (ref "IH6") (pin "8") (pinfunction "8_8") (pintype "passive"))
    )
    (net (code "136") (name "Net-(D20-Pad1)") (class "Default")
      (node (ref "D20") (pin "1") (pinfunction "1_1") (pintype "passive"))
      (node (ref "IH7") (pin "2") (pinfunction "2_2") (pintype "passive"))
    )
    (net (code "137") (name "Net-(D20-Pad2)") (class "Default")
      (node (ref "D20") (pin "2") (pinfunction "2_2") (pintype "passive"))
      (node (ref "IH7") (pin "8") (pinfunction "8_8") (pintype "passive"))
    )
    (net (code "138") (name "Net-(D21-Pad1)") (class "Default")
      (node (ref "D21") (pin "1") (pinfunction "1_1") (pintype "passive"))
      (node (ref "IH8") (pin "2") (pinfunction "2_2") (pintype "passive"))
    )
    (net (code "139") (name "Net-(D21-Pad2)") (class "Default")
      (node (ref "D21") (pin "2") (pinfunction "2_2") (pintype "passive"))
      (node (ref "IH8") (pin "8") (pinfunction "8_8") (pintype "passive"))
    )
    (net (code "140") (name "Net-(D22-Pad1)") (class "Default")
      (node (ref "D22") (pin "1") (pinfunction "1_1") (pintype "passive"))
      (node (ref "IH5") (pin "4") (pinfunction "4_4") (pintype "passive"))
    )
    (net (code "141") (name "Net-(D22-Pad2)") (class "Default")
      (node (ref "D22") (pin "2") (pinfunction "2_2") (pintype "passive"))
      (node (ref "IH5") (pin "6") (pinfunction "6_6") (pintype "passive"))
    )
    (net (code "142") (name "Net-(D23-Pad1)") (class "Default")
      (node (ref "D23") (pin "1") (pinfunction "1_1") (pintype "passive"))
      (node (ref "IH6") (pin "4") (pinfunction "4_4") (pintype "passive"))
    )
    (net (code "143") (name "Net-(D23-Pad2)") (class "Default")
      (node (ref "D23") (pin "2") (pinfunction "2_2") (pintype "passive"))
      (node (ref "IH6") (pin "6") (pinfunction "6_6") (pintype "passive"))
    )
    (net (code "144") (name "Net-(D24-Pad1)") (class "Default")
      (node (ref "D24") (pin "1") (pinfunction "1_1") (pintype "passive"))
      (node (ref "IH7") (pin "4") (pinfunction "4_4") (pintype "passive"))
    )
    (net (code "145") (name "Net-(D24-Pad2)") (class "Default")
      (node (ref "D24") (pin "2") (pinfunction "2_2") (pintype "passive"))
      (node (ref "IH7") (pin "6") (pinfunction "6_6") (pintype "passive"))
    )
    (net (code "146") (name "Net-(D25-Pad1)") (class "Default")
      (node (ref "D25") (pin "1") (pinfunction "1_1") (pintype "passive"))
      (node (ref "IH8") (pin "4") (pinfunction "4_4") (pintype "passive"))
    )
    (net (code "147") (name "Net-(D25-Pad2)") (class "Default")
      (node (ref "D25") (pin "2") (pinfunction "2_2") (pintype "passive"))
      (node (ref "IH8") (pin "6") (pinfunction "6_6") (pintype "passive"))
    )
    (net (code "148") (name "Net-(D26-Pad1)") (class "Default")
      (node (ref "D26") (pin "1") (pinfunction "1_1") (pintype "passive"))
      (node (ref "IH5") (pin "10") (pinfunction "10_10") (pintype "passive"))
    )
    (net (code "149") (name "Net-(D26-Pad2)") (class "Default")
      (node (ref "D26") (pin "2") (pinfunction "2_2") (pintype "passive"))
      (node (ref "IH5") (pin "16") (pinfunction "16_16") (pintype "passive"))
    )
    (net (code "150") (name "Net-(D27-Pad1)") (class "Default")
      (node (ref "D27") (pin "1") (pinfunction "1_1") (pintype "passive"))
      (node (ref "IH6") (pin "10") (pinfunction "10_10") (pintype "passive"))
    )
    (net (code "151") (name "Net-(D27-Pad2)") (class "Default")
      (node (ref "D27") (pin "2") (pinfunction "2_2") (pintype "passive"))
      (node (ref "IH6") (pin "16") (pinfunction "16_16") (pintype "passive"))
    )
    (net (code "152") (name "Net-(D28-Pad1)") (class "Default")
      (node (ref "D28") (pin "1") (pinfunction "1_1") (pintype "passive"))
      (node (ref "IH7") (pin "10") (pinfunction "10_10") (pintype "passive"))
    )
    (net (code "153") (name "Net-(D28-Pad2)") (class "Default")
      (node (ref "D28") (pin "2") (pinfunction "2_2") (pintype "passive"))
      (node (ref "IH7") (pin "16") (pinfunction "16_16") (pintype "passive"))
    )
    (net (code "154") (name "Net-(D29-Pad1)") (class "Default")
      (node (ref "D29") (pin "1") (pinfunction "1_1") (pintype "passive"))
      (node (ref "IH8") (pin "10") (pinfunction "10_10") (pintype "passive"))
    )
    (net (code "155") (name "Net-(D29-Pad2)") (class "Default")
      (node (ref "D29") (pin "2") (pinfunction "2_2") (pintype "passive"))
      (node (ref "IH8") (pin "16") (pinfunction "16_16") (pintype "passive"))
    )
    (net (code "156") (name "Net-(D30-Pad1)") (class "Default")
      (node (ref "D30") (pin "1") (pinfunction "1_1") (pintype "passive"))
      (node (ref "IH5") (pin "12") (pinfunction "12_12") (pintype "passive"))
    )
    (net (code "157") (name "Net-(D30-Pad2)") (class "Default")
      (node (ref "D30") (pin "2") (pinfunction "2_2") (pintype "passive"))
      (node (ref "IH5") (pin "14") (pinfunction "14_14") (pintype "passive"))
    )
    (net (code "158") (name "Net-(D31-Pad1)") (class "Default")
      (node (ref "D31") (pin "1") (pinfunction "1_1") (pintype "passive"))
      (node (ref "IH6") (pin "12") (pinfunction "12_12") (pintype "passive"))
    )
    (net (code "159") (name "Net-(D31-Pad2)") (class "Default")
      (node (ref "D31") (pin "2") (pinfunction "2_2") (pintype "passive"))
      (node (ref "IH6") (pin "14") (pinfunction "14_14") (pintype "passive"))
    )
    (net (code "160") (name "Net-(D32-Pad1)") (class "Default")
      (node (ref "D32") (pin "1") (pinfunction "1_1") (pintype "passive"))
      (node (ref "IH7") (pin "12") (pinfunction "12_12") (pintype "passive"))
    )
    (net (code "161") (name "Net-(D32-Pad2)") (class "Default")
      (node (ref "D32") (pin "2") (pinfunction "2_2") (pintype "passive"))
      (node (ref "IH7") (pin "14") (pinfunction "14_14") (pintype "passive"))
    )
    (net (code "162") (name "Net-(D33-Pad1)") (class "Default")
      (node (ref "D33") (pin "1") (pinfunction "1_1") (pintype "passive"))
      (node (ref "IH8") (pin "12") (pinfunction "12_12") (pintype "passive"))
    )
    (net (code "163") (name "Net-(D33-Pad2)") (class "Default")
      (node (ref "D33") (pin "2") (pinfunction "2_2") (pintype "passive"))
      (node (ref "IH8") (pin "14") (pinfunction "14_14") (pintype "passive"))
    )
    (net (code "164") (name "Net-(D35-PadA)") (class "Default")
      (node (ref "D35") (pin "A") (pinfunction "A_A") (pintype "passive"))
      (node (ref "R6") (pin "1") (pinfunction "1_1") (pintype "passive"))
    )
    (net (code "165") (name "Net-(D36-PadA)") (class "Default")
      (node (ref "D36") (pin "A") (pinfunction "A_A") (pintype "passive"))
      (node (ref "R7") (pin "1") (pinfunction "1_1") (pintype "passive"))
    )
    (net (code "166") (name "Net-(D37-PadA)") (class "Default")
      (node (ref "D37") (pin "A") (pinfunction "A_A") (pintype "passive"))
      (node (ref "R8") (pin "2") (pinfunction "2_2") (pintype "passive"))
    )
    (net (code "167") (name "Net-(U2-A)") (class "Default")
      (node (ref "D34") (pin "2") (pinfunction "2_2") (pintype "passive"))
      (node (ref "R5") (pin "2") (pinfunction "2_2") (pintype "passive"))
      (node (ref "U2") (pin "2") (pinfunction "A_2") (pintype "passive"))
    )
    (net (code "168") (name "Net-(U2-C)") (class "Default")
      (node (ref "CONN3") (pin "5") (pinfunction "5_5") (pintype "bidirectional"))
      (node (ref "D34") (pin "3") (pinfunction "3_3") (pintype "passive"))
      (node (ref "U2") (pin "3") (pinfunction "C_3") (pintype "passive"))
    )
    (net (code "169") (name "Net-(U3-CLK)") (class "Default")
      (node (ref "U3") (pin "13") (pinfunction "CLK_13") (pintype "input"))
      (node (ref "U7") (pin "8") (pinfunction "3Y_8") (pintype "bidirectional"))
    )
    (net (code "170") (name "Net-(U3-DIN)") (class "Default")
      (node (ref "U3") (pin "1") (pinfunction "DIN_1") (pintype "input"))
      (node (ref "U7") (pin "3") (pinfunction "1Y_3") (pintype "bidirectional"))
    )
    (net (code "171") (name "Net-(U3-ISET)") (class "Default")
      (node (ref "R19") (pin "1") (pinfunction "1_1") (pintype "passive"))
      (node (ref "U3") (pin "18") (pinfunction "ISET_18") (pintype "input"))
    )
    (net (code "172") (name "Net-(U3-LOAD)") (class "Default")
      (node (ref "U3") (pin "12") (pinfunction "LOAD_12") (pintype "input"))
      (node (ref "U7") (pin "6") (pinfunction "2Y_6") (pintype "bidirectional"))
    )
    (net (code "173") (name "OSC_IN") (class "Default")
      (node (ref "C23") (pin "1") (pinfunction "1_1") (pintype "passive"))
      (node (ref "U1") (pin "5") (pinfunction "PH0_5") (pintype "bidirectional"))
      (node (ref "Y1") (pin "1") (pinfunction "1_1") (pintype "passive"))
    )
    (net (code "174") (name "OSC_OUT") (class "Default")
      (node (ref "C24") (pin "1") (pinfunction "1_1") (pintype "passive"))
      (node (ref "U1") (pin "6") (pinfunction "PH1_6") (pintype "bidirectional"))
      (node (ref "Y1") (pin "3") (pinfunction "2_3") (pintype "passive"))
    )
    (net (code "175") (name "SCL") (class "Default")
      (node (ref "CONN6") (pin "2") (pinfunction "2_2") (pintype "passive"))
      (node (ref "U1") (pin "58") (pinfunction "PB6_58") (pintype "bidirectional"))
    )
    (net (code "176") (name "SDA") (class "Default")
      (node (ref "CONN6") (pin "1") (pinfunction "1_1") (pintype "passive"))
      (node (ref "U1") (pin "59") (pinfunction "PB7_59") (pintype "bidirectional"))
    )
    (net (code "177") (name "SWDCLK") (class "Default")
      (node (ref "CONN8") (pin "3") (pinfunction "3_3") (pintype "passive"))
      (node (ref "U1") (pin "49") (pinfunction "PA14_49") (pintype "bidirectional"))
    )
    (net (code "178") (name "SWDIO") (class "Default")
      (node (ref "CONN8") (pin "1") (pinfunction "1_1") (pintype "passive"))
      (node (ref "U1") (pin "46") (pinfunction "PA13_46") (pintype "bidirectional"))
    )
    (net (code "179") (name "UART_RX") (class "Default")
      (node (ref "CONN7") (pin "1") (pinfunction "1_1") (pintype "passive"))
      (node (ref "U1") (pin "54") (pinfunction "PD2_54") (pintype "bidirectional"))
    )
    (net (code "180") (name "UART_TX") (class "Default")
      (node (ref "CONN7") (pin "2") (pinfunction "2_2") (pintype "passive"))
      (node (ref "U1") (pin "53") (pinfunction "PC12_53") (pintype "bidirectional"))
    )
    (net (code "181") (name "USB_SHIELD") (class "Default")
      (node (ref "CONN1") (pin "S1") (pinfunction "S_S1") (pintype "passive"))
      (node (ref "CONN1") (pin "S2") (pinfunction "S_S2") (pintype "passive"))
      (node (ref "L1") (pin "2") (pinfunction "2_2") (pintype "passive"))
    )
    (net (code "182") (name "unconnected-(CONN3-Pad1)") (class "Default")
      (node (ref "CONN3") (pin "1") (pinfunction "1_1") (pintype "bidirectional"))
    )
    (net (code "183") (name "unconnected-(CONN3-Pad2)") (class "Default")
      (node (ref "CONN3") (pin "2") (pinfunction "2_2") (pintype "passive"))
    )
    (net (code "184") (name "unconnected-(CONN3-Pad3)") (class "Default")
      (node (ref "CONN3") (pin "3") (pinfunction "3_3") (pintype "bidirectional"))
    )
    (net (code "185") (name "unconnected-(CONN4-Pad1)") (class "Default")
      (node (ref "CONN4") (pin "1") (pinfunction "1_1") (pintype "bidirectional"))
    )
    (net (code "186") (name "unconnected-(CONN4-Pad3)") (class "Default")
      (node (ref "CONN4") (pin "3") (pinfunction "3_3") (pintype "bidirectional"))
    )
    (net (code "187") (name "unconnected-(D34-Pad1)") (class "Default")
      (node (ref "D34") (pin "1") (pinfunction "1_1") (pintype "passive"))
    )
    (net (code "188") (name "unconnected-(U1-PA15-Pad50)") (class "Default")
      (node (ref "U1") (pin "50") (pinfunction "PA15_50") (pintype "bidirectional"))
    )
    (net (code "189") (name "unconnected-(U1-PB3-Pad55)") (class "Default")
      (node (ref "U1") (pin "55") (pinfunction "PB3_55") (pintype "bidirectional"))
    )
    (net (code "190") (name "unconnected-(U1-PB5-Pad57)") (class "Default")
      (node (ref "U1") (pin "57") (pinfunction "PB5_57") (pintype "bidirectional"))
    )
    (net (code "191") (name "unconnected-(U1-PC0-Pad8)") (class "Default")
      (node (ref "U1") (pin "8") (pinfunction "PC0_8") (pintype "bidirectional"))
    )
    (net (code "192") (name "unconnected-(U1-PC3-Pad11)") (class "Default")
      (node (ref "U1") (pin "11") (pinfunction "PC3_11") (pintype "bidirectional"))
    )
    (net (code "193") (name "unconnected-(U1-PC10-Pad51)") (class "Default")
      (node (ref "U1") (pin "51") (pinfunction "PC10_51") (pintype "bidirectional"))
    )
    (net (code "194") (name "unconnected-(U1-PC11-Pad52)") (class "Default")
      (node (ref "U1") (pin "52") (pinfunction "PC11_52") (pintype "bidirectional"))
    )
    (net (code "195") (name "unconnected-(U1-PC13-Pad2)") (class "Default")
      (node (ref "U1") (pin "2") (pinfunction "PC13_2") (pintype "bidirectional"))
    )
    (net (code "196") (name "unconnected-(U1-PC14-Pad3)") (class "Default")
      (node (ref "U1") (pin "3") (pinfunction "PC14_3") (pintype "bidirectional"))
    )
    (net (code "197") (name "unconnected-(U1-PC15-Pad4)") (class "Default")
      (node (ref "U1") (pin "4") (pinfunction "PC15_4") (pintype "bidirectional"))
    )
    (net (code "198") (name "unconnected-(U3-DOUT-Pad24)") (class "Default")
      (node (ref "U3") (pin "24") (pinfunction "DOUT_24") (pintype "output"))
    )
    (net (code "199") (name "unconnected-(U3-SEG_A-Pad14)") (class "Default")
      (node (ref "U3") (pin "14") (pinfunction "SEG_A_14") (pintype "output"))
    )
    (net (code "200") (name "unconnected-(U3-SEG_F-Pad15)") (class "Default")
      (node (ref "U3") (pin "15") (pinfunction "SEG_F_15") (pintype "output"))
    )
    (net (code "201") (name "unconnected-(U7A-4A-Pad12)") (class "Default")
      (node (ref "U7") (pin "12") (pinfunction "4A_12") (pintype "bidirectional"))
    )
    (net (code "202") (name "unconnected-(U7A-4Y-Pad11)") (class "Default")
      (node (ref "U7") (pin "11") (pinfunction "4Y_11") (pintype "bidirectional"))
    )
    (net (code "203") (name "unconnected-(U7A-4~{(OE})-Pad13)") (class "Default")
      (node (ref "U7") (pin "13") (pinfunction "4~{(OE})_13") (pintype "bidirectional"))
    )
    (net (code "204") (name "unconnected-(VR2-ADJ-Pad4)") (class "Default")
      (node (ref "VR2") (pin "4") (pinfunction "ADJ_4") (pintype "passive"))
    )
  )
)
